# SCH__V2_0.net
KiCad netlist of a schematic drawn in EasyEDA
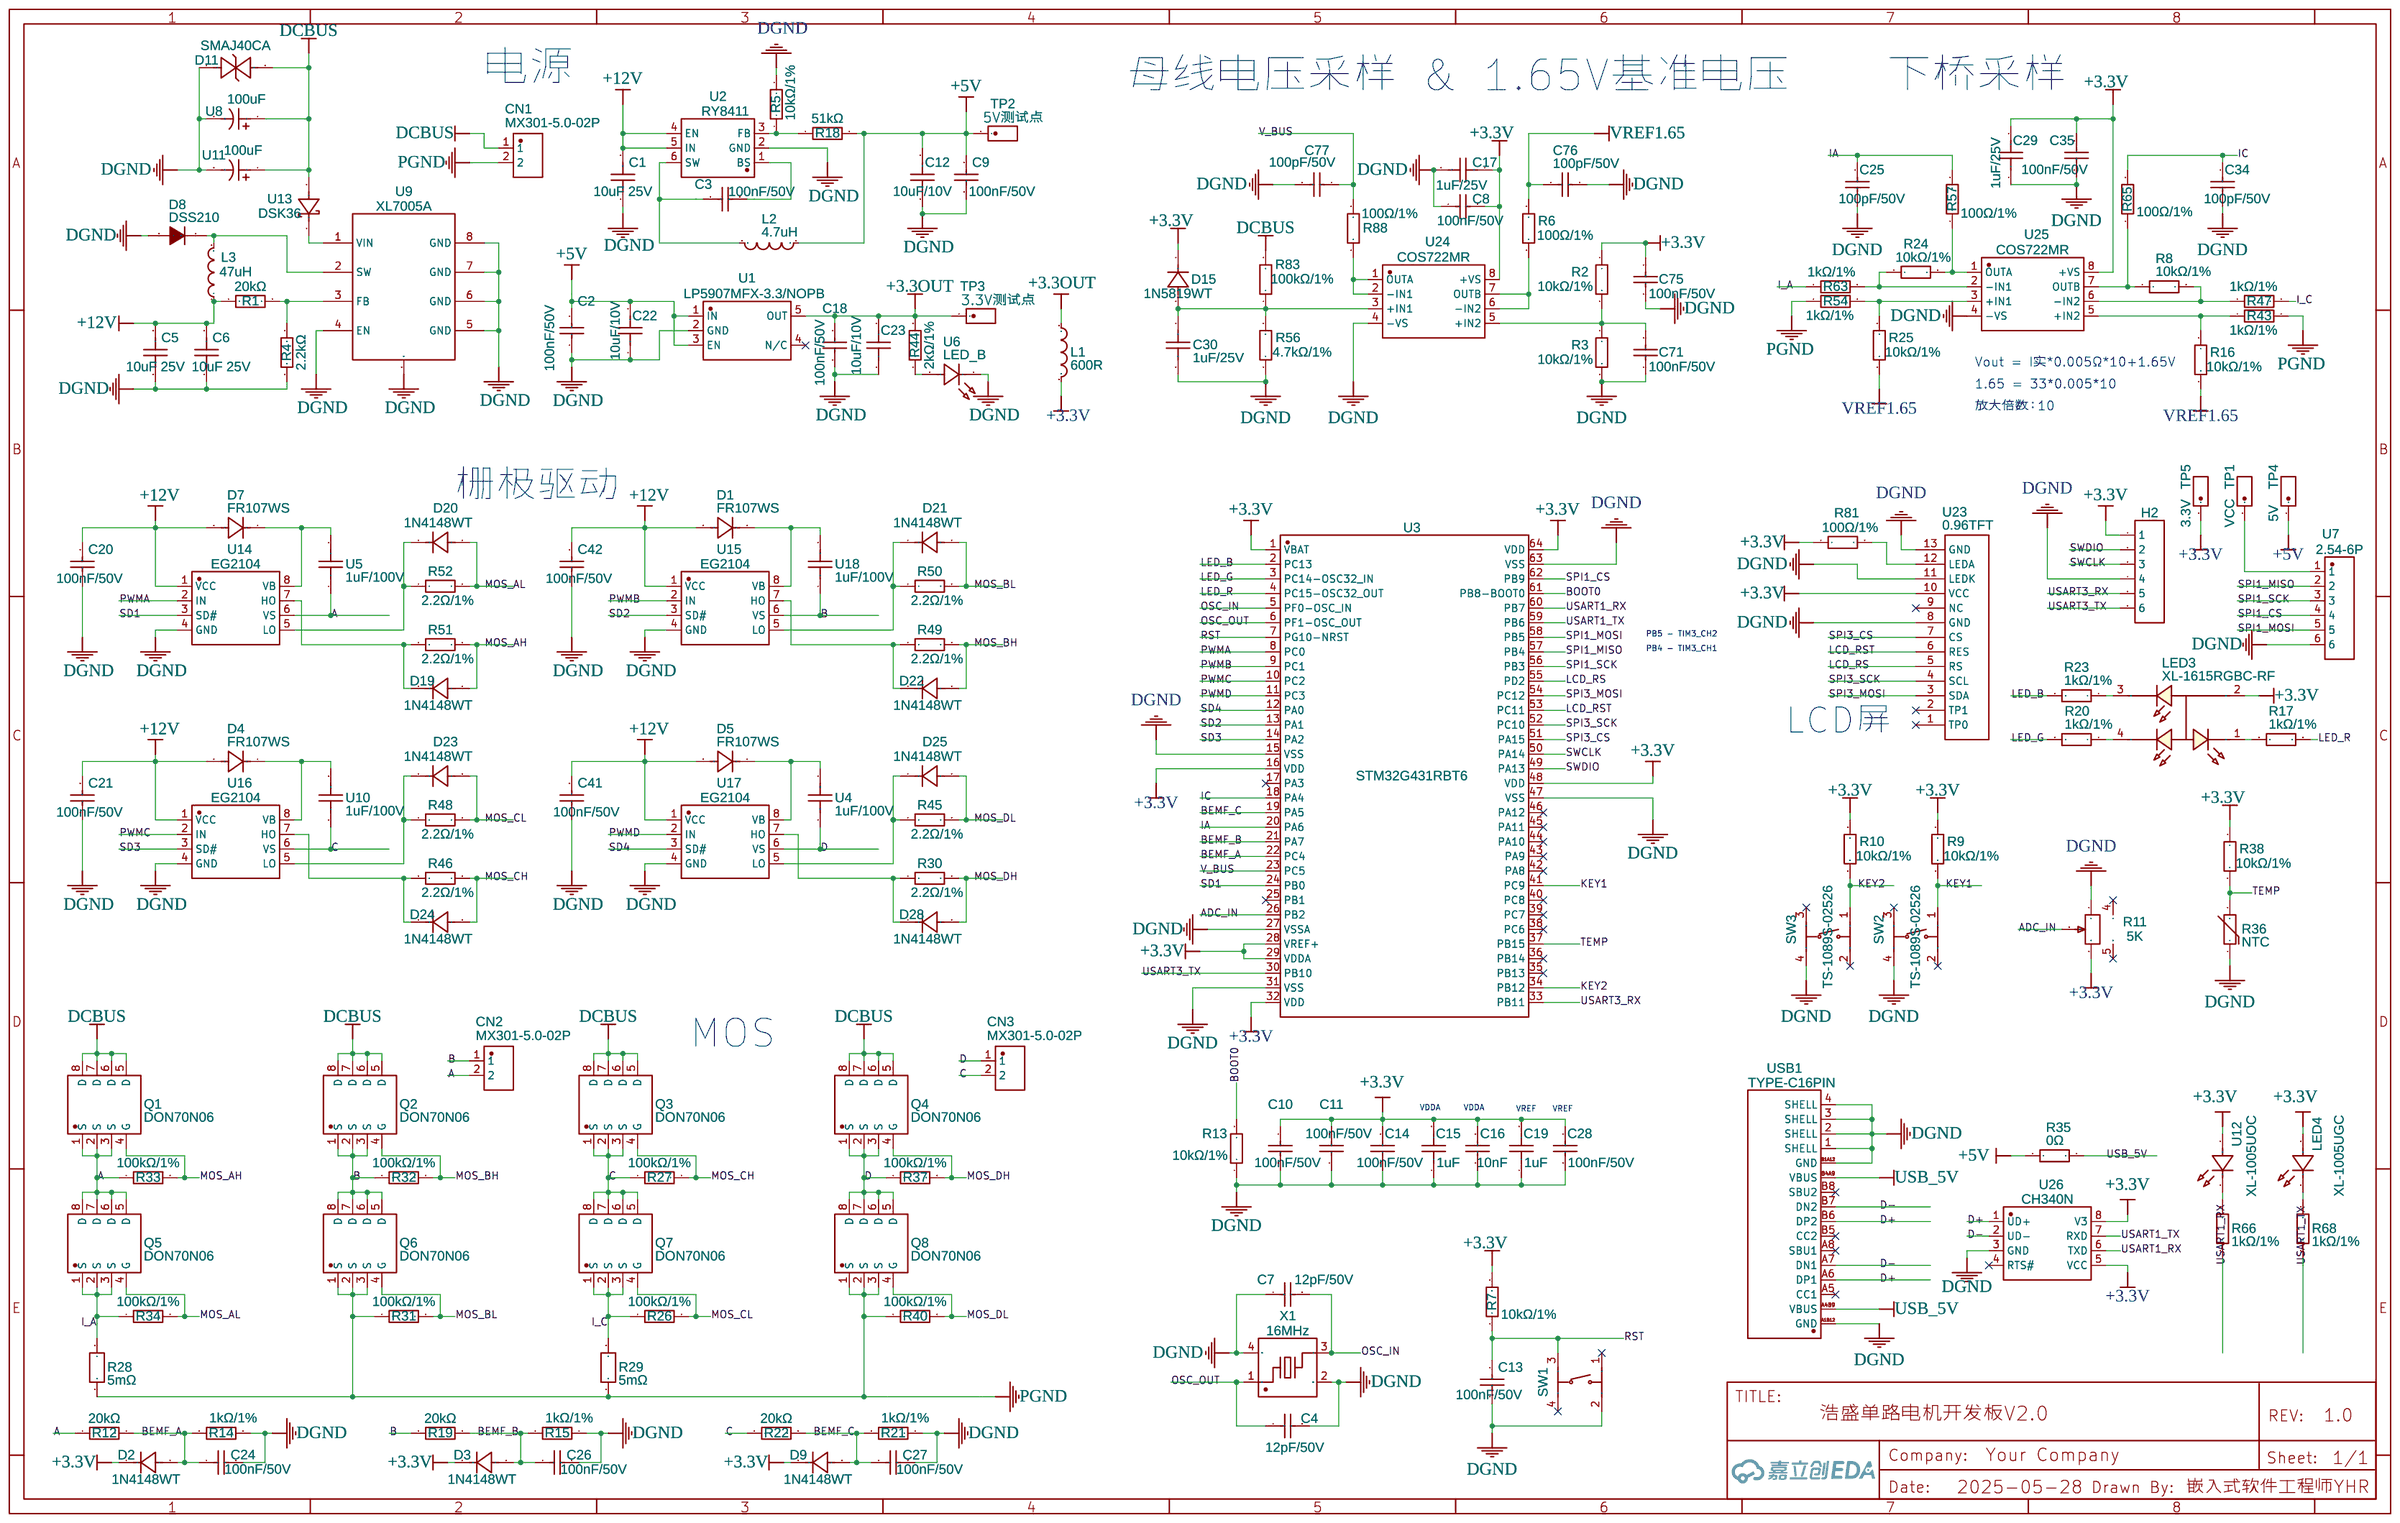
[diagram p0: schematic sheet]

(export (version "E")
  (design (tool "Eeschema 10.0.6"))
  (components
    (comp (ref "C1")
      (value "10uF 25V")
      (fields
        (field (name "Manufacturer Part") "HGC0603R5106M250NTHJ")
        (field (name "Manufacturer") "Chinocera(华瓷)")
      )
      (libsource (lib "") (part "HGC0603R5106M250NTHJ"))
    )
    (comp (ref "C2")
      (value "100nF/50V")
      (fields
        (field (name "Manufacturer Part") "CC0402KRX7R9BB104")
        (field (name "Manufacturer") "YAGEO(国巨)")
      )
      (libsource (lib "") (part "CC0402KRX7R9BB104"))
    )
    (comp (ref "C3")
      (value "100nF/50V")
      (fields
        (field (name "Manufacturer Part") "CC0402KRX7R9BB104")
        (field (name "Manufacturer") "YAGEO(国巨)")
      )
      (libsource (lib "") (part "CC0402KRX7R9BB104_3"))
    )
    (comp (ref "C4")
      (value "12pF/50V")
      (fields
        (field (name "Manufacturer Part") "CC0402JRNPO9BN120")
        (field (name "Manufacturer") "YAGEO(国巨)")
      )
      (libsource (lib "") (part "CC0402JRNPO9BN120"))
    )
    (comp (ref "C5")
      (value "10uF 25V")
      (fields
        (field (name "Manufacturer Part") "HGC0603R5106M250NTHJ")
        (field (name "Manufacturer") "Chinocera(华瓷)")
      )
      (libsource (lib "") (part "HGC0603R5106M250NTHJ"))
    )
    (comp (ref "C6")
      (value "10uF 25V")
      (fields
        (field (name "Manufacturer Part") "HGC0603R5106M250NTHJ")
        (field (name "Manufacturer") "Chinocera(华瓷)")
      )
      (libsource (lib "") (part "HGC0603R5106M250NTHJ"))
    )
    (comp (ref "C7")
      (value "12pF/50V")
      (fields
        (field (name "Manufacturer Part") "CC0402JRNPO9BN120")
        (field (name "Manufacturer") "YAGEO(国巨)")
      )
      (libsource (lib "") (part "CC0402JRNPO9BN120"))
    )
    (comp (ref "C8")
      (value "100nF/50V")
      (fields
        (field (name "Manufacturer Part") "CC0402KRX7R9BB104")
        (field (name "Manufacturer") "YAGEO(国巨)")
      )
      (libsource (lib "") (part "CC0402KRX7R9BB104_1"))
    )
    (comp (ref "C9")
      (value "100nF/50V")
      (fields
        (field (name "Manufacturer Part") "CC0402KRX7R9BB104")
        (field (name "Manufacturer") "YAGEO(国巨)")
      )
      (libsource (lib "") (part "CC0402KRX7R9BB104"))
    )
    (comp (ref "C10")
      (value "100nF/50V")
      (fields
        (field (name "Manufacturer Part") "CC0402KRX7R9BB104")
        (field (name "Manufacturer") "YAGEO(国巨)")
      )
      (libsource (lib "") (part "CC0402KRX7R9BB104"))
    )
    (comp (ref "C11")
      (value "100nF/50V")
      (fields
        (field (name "Manufacturer Part") "CC0402KRX7R9BB104")
        (field (name "Manufacturer") "YAGEO(国巨)")
      )
      (libsource (lib "") (part "CC0402KRX7R9BB104"))
    )
    (comp (ref "C12")
      (value "10uF/10V")
      (fields
        (field (name "Manufacturer Part") "CL05A106MP5NUNC")
        (field (name "Manufacturer") "SAMSUNG(三星)")
      )
      (libsource (lib "") (part "CL05A106MP5NUNC_C315248"))
    )
    (comp (ref "C13")
      (value "100nF/50V")
      (fields
        (field (name "Manufacturer Part") "CC0402KRX7R9BB104")
        (field (name "Manufacturer") "YAGEO(国巨)")
      )
      (libsource (lib "") (part "CC0402KRX7R9BB104_2"))
    )
    (comp (ref "C14")
      (value "100nF/50V")
      (fields
        (field (name "Manufacturer Part") "CC0402KRX7R9BB104")
        (field (name "Manufacturer") "YAGEO(国巨)")
      )
      (libsource (lib "") (part "CC0402KRX7R9BB104"))
    )
    (comp (ref "C15")
      (value "1uF")
      (fields
        (field (name "Manufacturer Part") "CC0402KRX5R8BB105")
        (field (name "Manufacturer") "YAGEO(国巨)")
      )
      (libsource (lib "") (part "CC0402KRX5R8BB105"))
    )
    (comp (ref "C16")
      (value "10nF")
      (fields
        (field (name "Manufacturer Part") "CC0402KRX7R9BB103")
        (field (name "Manufacturer") "YAGEO(国巨)")
      )
      (libsource (lib "") (part "CC0402KRX7R9BB103"))
    )
    (comp (ref "C17")
      (value "1uF/25V")
      (fields
        (field (name "Manufacturer Part") "CL05A105KA5NQNC")
        (field (name "Manufacturer") "SAMSUNG(三星)")
      )
      (libsource (lib "") (part "CL05A105KA5NQNC_2"))
    )
    (comp (ref "C18")
      (value "100nF/50V")
      (fields
        (field (name "Manufacturer Part") "CC0402KRX7R9BB104")
        (field (name "Manufacturer") "YAGEO(国巨)")
      )
      (libsource (lib "") (part "CC0402KRX7R9BB104"))
    )
    (comp (ref "C19")
      (value "1uF")
      (fields
        (field (name "Manufacturer Part") "CC0402KRX5R8BB105")
        (field (name "Manufacturer") "YAGEO(国巨)")
      )
      (libsource (lib "") (part "CC0402KRX5R8BB105"))
    )
    (comp (ref "C20")
      (value "100nF/50V")
      (fields
        (field (name "Manufacturer Part") "CC0402KRX7R9BB104")
        (field (name "Manufacturer") "YAGEO(国巨)")
      )
      (libsource (lib "") (part "CC0402KRX7R9BB104"))
    )
    (comp (ref "C21")
      (value "100nF/50V")
      (fields
        (field (name "Manufacturer Part") "CC0402KRX7R9BB104")
        (field (name "Manufacturer") "YAGEO(国巨)")
      )
      (libsource (lib "") (part "CC0402KRX7R9BB104"))
    )
    (comp (ref "C22")
      (value "10uF/10V")
      (fields
        (field (name "Manufacturer Part") "CL05A106MP5NUNC")
        (field (name "Manufacturer") "SAMSUNG(三星)")
      )
      (libsource (lib "") (part "CL05A106MP5NUNC_C315248"))
    )
    (comp (ref "C23")
      (value "10uF/10V")
      (fields
        (field (name "Manufacturer Part") "CL05A106MP5NUNC")
        (field (name "Manufacturer") "SAMSUNG(三星)")
      )
      (libsource (lib "") (part "CL05A106MP5NUNC_C315248_1"))
    )
    (comp (ref "C24")
      (value "100nF/50V")
      (fields
        (field (name "Manufacturer Part") "CC0402KRX7R9BB104")
        (field (name "Manufacturer") "YAGEO(国巨)")
      )
      (libsource (lib "") (part "CC0402KRX7R9BB104_1"))
    )
    (comp (ref "C25")
      (value "100pF/50V")
      (fields
        (field (name "Manufacturer Part") "CC0402JRNPO9BN101")
        (field (name "Manufacturer") "YAGEO(国巨)")
      )
      (libsource (lib "") (part "CC0402JRNPO9BN101"))
    )
    (comp (ref "C26")
      (value "100nF/50V")
      (fields
        (field (name "Manufacturer Part") "CC0402KRX7R9BB104")
        (field (name "Manufacturer") "YAGEO(国巨)")
      )
      (libsource (lib "") (part "CC0402KRX7R9BB104_1"))
    )
    (comp (ref "C27")
      (value "100nF/50V")
      (fields
        (field (name "Manufacturer Part") "CC0402KRX7R9BB104")
        (field (name "Manufacturer") "YAGEO(国巨)")
      )
      (libsource (lib "") (part "CC0402KRX7R9BB104_1"))
    )
    (comp (ref "C28")
      (value "100nF/50V")
      (fields
        (field (name "Manufacturer Part") "CC0402KRX7R9BB104")
        (field (name "Manufacturer") "YAGEO(国巨)")
      )
      (libsource (lib "") (part "CC0402KRX7R9BB104"))
    )
    (comp (ref "C29")
      (value "1uF/25V")
      (fields
        (field (name "Manufacturer Part") "CL05A105KA5NQNC")
        (field (name "Manufacturer") "SAMSUNG(三星)")
      )
      (libsource (lib "") (part "CL05A105KA5NQNC"))
    )
    (comp (ref "C30")
      (value "1uF/25V")
      (fields
        (field (name "Manufacturer Part") "CL05A105KA5NQNC")
        (field (name "Manufacturer") "SAMSUNG(三星)")
      )
      (libsource (lib "") (part "CL05A105KA5NQNC_1"))
    )
    (comp (ref "C34")
      (value "100pF/50V")
      (fields
        (field (name "Manufacturer Part") "CC0402JRNPO9BN101")
        (field (name "Manufacturer") "YAGEO(国巨)")
      )
      (libsource (lib "") (part "CC0402JRNPO9BN101"))
    )
    (comp (ref "C35")
      (value "100nF/50V")
      (fields
        (field (name "Manufacturer Part") "CC0402KRX7R9BB104")
        (field (name "Manufacturer") "YAGEO(国巨)")
      )
      (libsource (lib "") (part "CC0402KRX7R9BB104_2"))
    )
    (comp (ref "C41")
      (value "100nF/50V")
      (fields
        (field (name "Manufacturer Part") "CC0402KRX7R9BB104")
        (field (name "Manufacturer") "YAGEO(国巨)")
      )
      (libsource (lib "") (part "CC0402KRX7R9BB104"))
    )
    (comp (ref "C42")
      (value "100nF/50V")
      (fields
        (field (name "Manufacturer Part") "CC0402KRX7R9BB104")
        (field (name "Manufacturer") "YAGEO(国巨)")
      )
      (libsource (lib "") (part "CC0402KRX7R9BB104"))
    )
    (comp (ref "C71")
      (value "100nF/50V")
      (fields
        (field (name "Manufacturer Part") "CC0402KRX7R9BB104")
        (field (name "Manufacturer") "YAGEO(国巨)")
      )
      (libsource (lib "") (part "CC0402KRX7R9BB104"))
    )
    (comp (ref "C75")
      (value "100nF/50V")
      (fields
        (field (name "Manufacturer Part") "CC0402KRX7R9BB104")
        (field (name "Manufacturer") "YAGEO(国巨)")
      )
      (libsource (lib "") (part "CC0402KRX7R9BB104"))
    )
    (comp (ref "C76")
      (value "100pF/50V")
      (fields
        (field (name "Manufacturer Part") "CC0402JRNPO9BN101")
        (field (name "Manufacturer") "YAGEO(国巨)")
      )
      (libsource (lib "") (part "CC0402JRNPO9BN101_1"))
    )
    (comp (ref "C77")
      (value "100pF/50V")
      (fields
        (field (name "Manufacturer Part") "CC0402JRNPO9BN101")
        (field (name "Manufacturer") "YAGEO(国巨)")
      )
      (libsource (lib "") (part "CC0402JRNPO9BN101_1"))
    )
    (comp (ref "CN1")
      (value "MX301-5.0-02P")
      (fields
        (field (name "Manufacturer Part") "MX301-5.0-02P-BU01-Cu-Y-A")
        (field (name "Manufacturer") "MAX(迈旭)")
      )
      (libsource (lib "") (part "MX301-5.0-02P-BU01-CU-Y-A"))
    )
    (comp (ref "CN2")
      (value "MX301-5.0-02P")
      (fields
        (field (name "Manufacturer Part") "MX301-5.0-02P-BU01-Cu-Y-A")
        (field (name "Manufacturer") "MAX(迈旭)")
      )
      (libsource (lib "") (part "MX301-5.0-02P-BU01-CU-Y-A"))
    )
    (comp (ref "CN3")
      (value "MX301-5.0-02P")
      (fields
        (field (name "Manufacturer Part") "MX301-5.0-02P-BU01-Cu-Y-A")
        (field (name "Manufacturer") "MAX(迈旭)")
      )
      (libsource (lib "") (part "MX301-5.0-02P-BU01-CU-Y-A"))
    )
    (comp (ref "D1")
      (value "FR107WS")
      (fields (field (name "Manufacturer") "YFW(佑风微)"))
      (libsource (lib "") (part "FR107WS_C3013756"))
    )
    (comp (ref "D2")
      (value "1N4148WT")
      (fields (field (name "Manufacturer") "TECH PUBLIC(台舟)"))
      (libsource (lib "") (part "1N4148WT_C708767"))
    )
    (comp (ref "D3")
      (value "1N4148WT")
      (fields (field (name "Manufacturer") "TECH PUBLIC(台舟)"))
      (libsource (lib "") (part "1N4148WT_C708767"))
    )
    (comp (ref "D4")
      (value "FR107WS")
      (fields (field (name "Manufacturer") "YFW(佑风微)"))
      (libsource (lib "") (part "FR107WS_C3013756"))
    )
    (comp (ref "D5")
      (value "FR107WS")
      (fields (field (name "Manufacturer") "YFW(佑风微)"))
      (libsource (lib "") (part "FR107WS_C3013756"))
    )
    (comp (ref "D7")
      (value "FR107WS")
      (fields (field (name "Manufacturer") "YFW(佑风微)"))
      (libsource (lib "") (part "FR107WS_C3013756"))
    )
    (comp (ref "D8")
      (value "DSS210")
      (fields (field (name "Manufacturer") "BORN(伯恩半导体)"))
      (libsource (lib "") (part "DSS210"))
    )
    (comp (ref "D9")
      (value "1N4148WT")
      (fields (field (name "Manufacturer") "TECH PUBLIC(台舟)"))
      (libsource (lib "") (part "1N4148WT_C708767"))
    )
    (comp (ref "D11")
      (value "SMAJ40CA")
      (fields (field (name "Manufacturer") "宏嘉诚"))
      (libsource (lib "") (part "SMAJ40CA_C19077552"))
    )
    (comp (ref "D15")
      (value "1N5819WT")
      (fields (field (name "Manufacturer") "HXY MOSFET(华轩阳电子)"))
      (libsource (lib "") (part "1N5819WT_C5451630"))
    )
    (comp (ref "D19")
      (value "1N4148WT")
      (fields (field (name "Manufacturer") "TECH PUBLIC(台舟)"))
      (libsource (lib "") (part "1N4148WT_C708767"))
    )
    (comp (ref "D20")
      (value "1N4148WT")
      (fields (field (name "Manufacturer") "TECH PUBLIC(台舟)"))
      (libsource (lib "") (part "1N4148WT_C708767"))
    )
    (comp (ref "D21")
      (value "1N4148WT")
      (fields (field (name "Manufacturer") "TECH PUBLIC(台舟)"))
      (libsource (lib "") (part "1N4148WT_C708767"))
    )
    (comp (ref "D22")
      (value "1N4148WT")
      (fields (field (name "Manufacturer") "TECH PUBLIC(台舟)"))
      (libsource (lib "") (part "1N4148WT_C708767"))
    )
    (comp (ref "D23")
      (value "1N4148WT")
      (fields (field (name "Manufacturer") "TECH PUBLIC(台舟)"))
      (libsource (lib "") (part "1N4148WT_C708767"))
    )
    (comp (ref "D24")
      (value "1N4148WT")
      (fields (field (name "Manufacturer") "TECH PUBLIC(台舟)"))
      (libsource (lib "") (part "1N4148WT_C708767"))
    )
    (comp (ref "D25")
      (value "1N4148WT")
      (fields (field (name "Manufacturer") "TECH PUBLIC(台舟)"))
      (libsource (lib "") (part "1N4148WT_C708767"))
    )
    (comp (ref "D28")
      (value "1N4148WT")
      (fields (field (name "Manufacturer") "TECH PUBLIC(台舟)"))
      (libsource (lib "") (part "1N4148WT_C708767"))
    )
    (comp (ref "H2")
      (value "Header-Male-2.54_1x6")
      (fields (field (name "Manufacturer Part") "2.54-1x6P直针") (field (name "Manufacturer") "BOOMELE(博穆精密)"))
      (libsource (lib "") (part "Header-Male-2.54_1x6"))
    )
    (comp (ref "L1")
      (value "600R")
      (fields (field (name "Manufacturer Part") "BLM15AG601SN1D") (field (name "Manufacturer") "muRata(村田)"))
      (libsource (lib "") (part "BLM15AG601SN1D"))
    )
    (comp (ref "L2")
      (value "4.7uH")
      (fields
        (field (name "Manufacturer Part") "FHD4020S-4R7MT")
        (field (name "Manufacturer") "cjiang(长江微电)")
      )
      (libsource (lib "") (part "FHD4020S-4R7MT"))
    )
    (comp (ref "L3")
      (value "47uH")
      (fields
        (field (name "Manufacturer Part") "FHD4020S-470MT")
        (field (name "Manufacturer") "cjiang(长江微电)")
      )
      (libsource (lib "") (part "FHD4020S-470MT"))
    )
    (comp (ref "LED3")
      (value "XL-1615RGBC-RF")
      (fields (field (name "Manufacturer") "XINGLIGHT(成兴光)"))
      (libsource (lib "") (part "XL-1615RGBC-RF"))
    )
    (comp (ref "LED4")
      (value "XL-1005UGC")
      (fields (field (name "Manufacturer") "XINGLIGHT(成兴光)"))
      (libsource (lib "") (part "XL-1005UGC"))
    )
    (comp (ref "Q1")
      (value "DON70N06")
      (fields (field (name "Manufacturer") "DOINGTER(杜因特)"))
      (libsource (lib "") (part "DON70N06"))
    )
    (comp (ref "Q2")
      (value "DON70N06")
      (fields (field (name "Manufacturer") "DOINGTER(杜因特)"))
      (libsource (lib "") (part "DON70N06"))
    )
    (comp (ref "Q3")
      (value "DON70N06")
      (fields (field (name "Manufacturer") "DOINGTER(杜因特)"))
      (libsource (lib "") (part "DON70N06"))
    )
    (comp (ref "Q4")
      (value "DON70N06")
      (fields (field (name "Manufacturer") "DOINGTER(杜因特)"))
      (libsource (lib "") (part "DON70N06"))
    )
    (comp (ref "Q5")
      (value "DON70N06")
      (fields (field (name "Manufacturer") "DOINGTER(杜因特)"))
      (libsource (lib "") (part "DON70N06"))
    )
    (comp (ref "Q6")
      (value "DON70N06")
      (fields (field (name "Manufacturer") "DOINGTER(杜因特)"))
      (libsource (lib "") (part "DON70N06"))
    )
    (comp (ref "Q7")
      (value "DON70N06")
      (fields (field (name "Manufacturer") "DOINGTER(杜因特)"))
      (libsource (lib "") (part "DON70N06"))
    )
    (comp (ref "Q8")
      (value "DON70N06")
      (fields (field (name "Manufacturer") "DOINGTER(杜因特)"))
      (libsource (lib "") (part "DON70N06"))
    )
    (comp (ref "R1")
      (value "20kΩ")
      (fields (field (name "Manufacturer Part") "RC0402FR-0720KL") (field (name "Manufacturer") "YAGEO(国巨)"))
      (libsource (lib "") (part "RC0402FR-0720KL"))
    )
    (comp (ref "R2")
      (value "10kΩ/1%")
      (fields (field (name "Manufacturer Part") "RC0402FR-0710KL") (field (name "Manufacturer") "YAGEO(国巨)"))
      (libsource (lib "") (part "RC0402FR-0710KL"))
    )
    (comp (ref "R3")
      (value "10kΩ/1%")
      (fields (field (name "Manufacturer Part") "RC0402FR-0710KL") (field (name "Manufacturer") "YAGEO(国巨)"))
      (libsource (lib "") (part "RC0402FR-0710KL"))
    )
    (comp (ref "R4")
      (value "2.2kΩ")
      (fields (field (name "Manufacturer Part") "RC0402FR-072K2L") (field (name "Manufacturer") "YAGEO(国巨)"))
      (libsource (lib "") (part "RC0402FR-072K2L"))
    )
    (comp (ref "R5")
      (value "10kΩ/1%")
      (fields (field (name "Manufacturer Part") "RC0402FR-0710KL") (field (name "Manufacturer") "YAGEO(国巨)"))
      (libsource (lib "") (part "RC0402FR-0710KL_1"))
    )
    (comp (ref "R6")
      (value "100Ω/1%")
      (fields (field (name "Manufacturer Part") "RC0402FR-07100RL") (field (name "Manufacturer") "YAGEO(国巨)"))
      (libsource (lib "") (part "RC0402FR-07100RL"))
    )
    (comp (ref "R7")
      (value "10kΩ/1%")
      (fields (field (name "Manufacturer Part") "RC0402FR-0710KL") (field (name "Manufacturer") "YAGEO(国巨)"))
      (libsource (lib "") (part "RC0402FR-0710KL_1"))
    )
    (comp (ref "R8")
      (value "10kΩ/1%")
      (fields (field (name "Manufacturer Part") "RC0402FR-0710KL") (field (name "Manufacturer") "YAGEO(国巨)"))
      (libsource (lib "") (part "RC0402FR-0710KL_2"))
    )
    (comp (ref "R9")
      (value "10kΩ/1%")
      (fields (field (name "Manufacturer Part") "RC0402FR-0710KL") (field (name "Manufacturer") "YAGEO(国巨)"))
      (libsource (lib "") (part "RC0402FR-0710KL"))
    )
    (comp (ref "R10")
      (value "10kΩ/1%")
      (fields (field (name "Manufacturer Part") "RC0402FR-0710KL") (field (name "Manufacturer") "YAGEO(国巨)"))
      (libsource (lib "") (part "RC0402FR-0710KL"))
    )
    (comp (ref "R11")
      (value "5K")
      (fields (field (name "Manufacturer Part") "R1001-B502-3P 18mm"))
      (libsource (lib "") (part "R1001-B502-3P 18mm"))
    )
    (comp (ref "R12")
      (value "20kΩ")
      (fields (field (name "Manufacturer Part") "RC0402FR-0720KL") (field (name "Manufacturer") "YAGEO(国巨)"))
      (libsource (lib "") (part "RC0402FR-0720KL"))
    )
    (comp (ref "R13")
      (value "10kΩ/1%")
      (fields (field (name "Manufacturer Part") "RC0402FR-0710KL") (field (name "Manufacturer") "YAGEO(国巨)"))
      (libsource (lib "") (part "RC0402FR-0710KL_1"))
    )
    (comp (ref "R14")
      (value "1kΩ/1%")
      (fields (field (name "Manufacturer Part") "RC0402FR-071KL") (field (name "Manufacturer") "YAGEO(国巨)"))
      (libsource (lib "") (part "RC0402FR-071KL_1"))
    )
    (comp (ref "R15")
      (value "1kΩ/1%")
      (fields (field (name "Manufacturer Part") "RC0402FR-071KL") (field (name "Manufacturer") "YAGEO(国巨)"))
      (libsource (lib "") (part "RC0402FR-071KL_1"))
    )
    (comp (ref "R16")
      (value "10kΩ/1%")
      (fields (field (name "Manufacturer Part") "RC0402FR-0710KL") (field (name "Manufacturer") "YAGEO(国巨)"))
      (libsource (lib "") (part "RC0402FR-0710KL"))
    )
    (comp (ref "R17")
      (value "1kΩ/1%")
      (fields (field (name "Manufacturer Part") "RC0402FR-071KL") (field (name "Manufacturer") "YAGEO(国巨)"))
      (libsource (lib "") (part "RC0402FR-071KL_1"))
    )
    (comp (ref "R18")
      (value "51kΩ")
      (fields (field (name "Manufacturer Part") "RC0402FR-0751KL") (field (name "Manufacturer") "YAGEO(国巨)"))
      (libsource (lib "") (part "RC0402FR-0751KL"))
    )
    (comp (ref "R19")
      (value "20kΩ")
      (fields (field (name "Manufacturer Part") "RC0402FR-0720KL") (field (name "Manufacturer") "YAGEO(国巨)"))
      (libsource (lib "") (part "RC0402FR-0720KL"))
    )
    (comp (ref "R20")
      (value "1kΩ/1%")
      (fields (field (name "Manufacturer Part") "RC0402FR-071KL") (field (name "Manufacturer") "YAGEO(国巨)"))
      (libsource (lib "") (part "RC0402FR-071KL_1"))
    )
    (comp (ref "R21")
      (value "1kΩ/1%")
      (fields (field (name "Manufacturer Part") "RC0402FR-071KL") (field (name "Manufacturer") "YAGEO(国巨)"))
      (libsource (lib "") (part "RC0402FR-071KL_1"))
    )
    (comp (ref "R22")
      (value "20kΩ")
      (fields (field (name "Manufacturer Part") "RC0402FR-0720KL") (field (name "Manufacturer") "YAGEO(国巨)"))
      (libsource (lib "") (part "RC0402FR-0720KL"))
    )
    (comp (ref "R23")
      (value "1kΩ/1%")
      (fields (field (name "Manufacturer Part") "RC0402FR-071KL") (field (name "Manufacturer") "YAGEO(国巨)"))
      (libsource (lib "") (part "RC0402FR-071KL_1"))
    )
    (comp (ref "R24")
      (value "10kΩ/1%")
      (fields (field (name "Manufacturer Part") "RC0402FR-0710KL") (field (name "Manufacturer") "YAGEO(国巨)"))
      (libsource (lib "") (part "RC0402FR-0710KL_2"))
    )
    (comp (ref "R25")
      (value "10kΩ/1%")
      (fields (field (name "Manufacturer Part") "RC0402FR-0710KL") (field (name "Manufacturer") "YAGEO(国巨)"))
      (libsource (lib "") (part "RC0402FR-0710KL"))
    )
    (comp (ref "R26")
      (value "100kΩ/1%")
      (fields (field (name "Manufacturer Part") "RC0402FR-07100KL") (field (name "Manufacturer") "YAGEO(国巨)"))
      (libsource (lib "") (part "RC0402FR-07100KL"))
    )
    (comp (ref "R27")
      (value "100kΩ/1%")
      (fields (field (name "Manufacturer Part") "RC0402FR-07100KL") (field (name "Manufacturer") "YAGEO(国巨)"))
      (libsource (lib "") (part "RC0402FR-07100KL"))
    )
    (comp (ref "R28")
      (value "5mΩ")
      (fields
        (field (name "Manufacturer Part") "HoJLR2512-3W-5mR-1%")
        (field (name "Manufacturer") "Milliohm(毫欧)")
      )
      (libsource (lib "") (part "HOJLR2512-3W-5MR-1%"))
    )
    (comp (ref "R29")
      (value "5mΩ")
      (fields
        (field (name "Manufacturer Part") "HoJLR2512-3W-5mR-1%")
        (field (name "Manufacturer") "Milliohm(毫欧)")
      )
      (libsource (lib "") (part "HOJLR2512-3W-5MR-1%"))
    )
    (comp (ref "R30")
      (value "2.2Ω/1%")
      (fields (field (name "Manufacturer Part") "RC0402FR-072R2L") (field (name "Manufacturer") "YAGEO(国巨)"))
      (libsource (lib "") (part "RC0402FR-072R2L"))
    )
    (comp (ref "R31")
      (value "100kΩ/1%")
      (fields (field (name "Manufacturer Part") "RC0402FR-07100KL") (field (name "Manufacturer") "YAGEO(国巨)"))
      (libsource (lib "") (part "RC0402FR-07100KL"))
    )
    (comp (ref "R32")
      (value "100kΩ/1%")
      (fields (field (name "Manufacturer Part") "RC0402FR-07100KL") (field (name "Manufacturer") "YAGEO(国巨)"))
      (libsource (lib "") (part "RC0402FR-07100KL"))
    )
    (comp (ref "R33")
      (value "100kΩ/1%")
      (fields (field (name "Manufacturer Part") "RC0402FR-07100KL") (field (name "Manufacturer") "YAGEO(国巨)"))
      (libsource (lib "") (part "RC0402FR-07100KL"))
    )
    (comp (ref "R34")
      (value "100kΩ/1%")
      (fields (field (name "Manufacturer Part") "RC0402FR-07100KL") (field (name "Manufacturer") "YAGEO(国巨)"))
      (libsource (lib "") (part "RC0402FR-07100KL"))
    )
    (comp (ref "R35")
      (value "0Ω")
      (fields
        (field (name "Manufacturer Part") "0402WGF0000TCE")
        (field (name "Manufacturer") "UNI-ROYAL(厚声)")
      )
      (libsource (lib "") (part "0402WGF0000TCE"))
    )
    (comp (ref "R36")
      (value "NTC")
      (fields (field (name "Manufacturer Part") "NCP15XH103F03RC") (field (name "Manufacturer") "muRata(村田)"))
      (libsource (lib "") (part "NCP15XH103F03RC"))
    )
    (comp (ref "R37")
      (value "100kΩ/1%")
      (fields (field (name "Manufacturer Part") "RC0402FR-07100KL") (field (name "Manufacturer") "YAGEO(国巨)"))
      (libsource (lib "") (part "RC0402FR-07100KL"))
    )
    (comp (ref "R38")
      (value "10kΩ/1%")
      (fields (field (name "Manufacturer Part") "RC0402FR-0710KL") (field (name "Manufacturer") "YAGEO(国巨)"))
      (libsource (lib "") (part "RC0402FR-0710KL"))
    )
    (comp (ref "R40")
      (value "100kΩ/1%")
      (fields (field (name "Manufacturer Part") "RC0402FR-07100KL") (field (name "Manufacturer") "YAGEO(国巨)"))
      (libsource (lib "") (part "RC0402FR-07100KL"))
    )
    (comp (ref "R43")
      (value "1kΩ/1%")
      (fields (field (name "Manufacturer Part") "RC0402FR-071KL") (field (name "Manufacturer") "YAGEO(国巨)"))
      (libsource (lib "") (part "RT0402BRD071K5L"))
    )
    (comp (ref "R44")
      (value "2kΩ/1%")
      (fields (field (name "Manufacturer Part") "RC0402FR-072KL") (field (name "Manufacturer") "YAGEO(国巨)"))
      (libsource (lib "") (part "RC0402FR-072KL"))
    )
    (comp (ref "R45")
      (value "2.2Ω/1%")
      (fields (field (name "Manufacturer Part") "RC0402FR-072R2L") (field (name "Manufacturer") "YAGEO(国巨)"))
      (libsource (lib "") (part "RC0402FR-072R2L"))
    )
    (comp (ref "R46")
      (value "2.2Ω/1%")
      (fields (field (name "Manufacturer Part") "RC0402FR-072R2L") (field (name "Manufacturer") "YAGEO(国巨)"))
      (libsource (lib "") (part "RC0402FR-072R2L"))
    )
    (comp (ref "R47")
      (value "1kΩ/1%")
      (fields (field (name "Manufacturer Part") "RC0402FR-071KL") (field (name "Manufacturer") "YAGEO(国巨)"))
      (libsource (lib "") (part "RT0402BRD071K5L"))
    )
    (comp (ref "R48")
      (value "2.2Ω/1%")
      (fields (field (name "Manufacturer Part") "RC0402FR-072R2L") (field (name "Manufacturer") "YAGEO(国巨)"))
      (libsource (lib "") (part "RC0402FR-072R2L"))
    )
    (comp (ref "R49")
      (value "2.2Ω/1%")
      (fields (field (name "Manufacturer Part") "RC0402FR-072R2L") (field (name "Manufacturer") "YAGEO(国巨)"))
      (libsource (lib "") (part "RC0402FR-072R2L"))
    )
    (comp (ref "R50")
      (value "2.2Ω/1%")
      (fields (field (name "Manufacturer Part") "RC0402FR-072R2L") (field (name "Manufacturer") "YAGEO(国巨)"))
      (libsource (lib "") (part "RC0402FR-072R2L"))
    )
    (comp (ref "R51")
      (value "2.2Ω/1%")
      (fields (field (name "Manufacturer Part") "RC0402FR-072R2L") (field (name "Manufacturer") "YAGEO(国巨)"))
      (libsource (lib "") (part "RC0402FR-072R2L"))
    )
    (comp (ref "R52")
      (value "2.2Ω/1%")
      (fields (field (name "Manufacturer Part") "RC0402FR-072R2L") (field (name "Manufacturer") "YAGEO(国巨)"))
      (libsource (lib "") (part "RC0402FR-072R2L"))
    )
    (comp (ref "R54")
      (value "1kΩ/1%")
      (fields (field (name "Manufacturer Part") "RC0402FR-071KL") (field (name "Manufacturer") "YAGEO(国巨)"))
      (libsource (lib "") (part "RT0402BRD071K5L"))
    )
    (comp (ref "R56")
      (value "4.7kΩ/1%")
      (fields (field (name "Manufacturer Part") "RC0402FR-074K7L") (field (name "Manufacturer") "YAGEO(国巨)"))
      (libsource (lib "") (part "RC0402FR-074K7L"))
    )
    (comp (ref "R57")
      (value "100Ω/1%")
      (fields (field (name "Manufacturer Part") "RC0402FR-07100RL") (field (name "Manufacturer") "YAGEO(国巨)"))
      (libsource (lib "") (part "RC0402FR-07100RL"))
    )
    (comp (ref "R63")
      (value "1kΩ/1%")
      (fields (field (name "Manufacturer Part") "RC0402FR-071KL") (field (name "Manufacturer") "YAGEO(国巨)"))
      (libsource (lib "") (part "RT0402BRD071K5L"))
    )
    (comp (ref "R65")
      (value "100Ω/1%")
      (fields (field (name "Manufacturer Part") "RC0402FR-07100RL") (field (name "Manufacturer") "YAGEO(国巨)"))
      (libsource (lib "") (part "RC0402FR-07100RL"))
    )
    (comp (ref "R66")
      (value "1kΩ/1%")
      (fields (field (name "Manufacturer Part") "RC0402FR-071KL") (field (name "Manufacturer") "YAGEO(国巨)"))
      (libsource (lib "") (part "RC0402FR-071KL"))
    )
    (comp (ref "R68")
      (value "1kΩ/1%")
      (fields (field (name "Manufacturer Part") "RC0402FR-071KL") (field (name "Manufacturer") "YAGEO(国巨)"))
      (libsource (lib "") (part "RC0402FR-071KL"))
    )
    (comp (ref "R81")
      (value "100Ω/1%")
      (fields (field (name "Manufacturer Part") "RC0402FR-07100RL") (field (name "Manufacturer") "YAGEO(国巨)"))
      (libsource (lib "") (part "RC0402FR-07100RL_1"))
    )
    (comp (ref "R83")
      (value "100kΩ/1%")
      (fields (field (name "Manufacturer Part") "RC0402FR-07100KL") (field (name "Manufacturer") "YAGEO(国巨)"))
      (libsource (lib "") (part "RC0402FR-07100KL_1"))
    )
    (comp (ref "R88")
      (value "100Ω/1%")
      (fields (field (name "Manufacturer Part") "RC0402FR-07100RL") (field (name "Manufacturer") "YAGEO(国巨)"))
      (libsource (lib "") (part "RC0402FR-07100RL"))
    )
    (comp (ref "SW1")
      (value "TS-1089S-02526")
      (fields (field (name "Manufacturer") "XUNPU(讯普)"))
      (libsource (lib "") (part "TS-1089S-02526"))
    )
    (comp (ref "SW2")
      (value "TS-1089S-02526")
      (fields (field (name "Manufacturer") "XUNPU(讯普)"))
      (libsource (lib "") (part "TS-1089S-02526"))
    )
    (comp (ref "SW3")
      (value "TS-1089S-02526")
      (fields (field (name "Manufacturer") "XUNPU(讯普)"))
      (libsource (lib "") (part "TS-1089S-02526"))
    )
    (comp (ref "TP1") (value "VCC") (libsource (lib "") (part "测试点")))
    (comp (ref "TP2") (value "5V测试点") (libsource (lib "") (part "测试点_1")))
    (comp (ref "TP3") (value "3.3V测试点") (libsource (lib "") (part "测试点_1")))
    (comp (ref "TP4") (value "5V") (libsource (lib "") (part "测试点")))
    (comp (ref "TP5") (value "3.3V") (libsource (lib "") (part "测试点")))
    (comp (ref "U1")
      (value "LP5907MFX-3.3/NOPB")
      (fields (field (name "Manufacturer") "TI(德州仪器)"))
      (libsource (lib "") (part "LP5907MFX-3.3/NOPB"))
    )
    (comp (ref "U2")
      (value "RY8411")
      (fields (field (name "Manufacturer") "RYCHiP(蕊源)"))
      (libsource (lib "") (part "RY8411_C2935411"))
    )
    (comp (ref "U3")
      (value "STM32G431RBT6")
      (fields (field (name "Manufacturer") "ST(意法半导体)"))
      (libsource (lib "") (part "STM32G431RBT6"))
    )
    (comp (ref "U4")
      (value "1uF/100V")
      (fields
        (field (name "Manufacturer Part") "CC0805KKX7R0BB105")
        (field (name "Manufacturer") "YAGEO(国巨)")
      )
      (libsource (lib "") (part "CC0805KKX7R0BB105"))
    )
    (comp (ref "U5")
      (value "1uF/100V")
      (fields
        (field (name "Manufacturer Part") "CC0805KKX7R0BB105")
        (field (name "Manufacturer") "YAGEO(国巨)")
      )
      (libsource (lib "") (part "CC0805KKX7R0BB105"))
    )
    (comp (ref "U6")
      (value "LED_B")
      (fields (field (name "Manufacturer Part") "XL-1005UBC") (field (name "Manufacturer") "XINGLIGHT(成兴光)"))
      (libsource (lib "") (part "XL-1005UBC_C22355736"))
    )
    (comp (ref "U7")
      (value "2.54-6P")
      (fields
        (field (name "Manufacturer Part") "DB125-2.54-6P-GN-S")
        (field (name "Manufacturer") "DORABO(地博电气)")
      )
      (libsource (lib "") (part "DB125-2.54-6P-GN"))
    )
    (comp (ref "U8")
      (value "100uF")
      (fields (field (name "Manufacturer Part") "189RV0092") (field (name "Manufacturer") "KNSCHA(科尼盛)"))
      (libsource (lib "") (part "189RV0092"))
    )
    (comp (ref "U9")
      (value "XL7005A")
      (fields (field (name "Manufacturer") "XLSEMI(芯龙)"))
      (libsource (lib "") (part "XL7005A"))
    )
    (comp (ref "U10")
      (value "1uF/100V")
      (fields
        (field (name "Manufacturer Part") "CC0805KKX7R0BB105")
        (field (name "Manufacturer") "YAGEO(国巨)")
      )
      (libsource (lib "") (part "CC0805KKX7R0BB105"))
    )
    (comp (ref "U11")
      (value "100uF")
      (fields (field (name "Manufacturer Part") "189RV0092") (field (name "Manufacturer") "KNSCHA(科尼盛)"))
      (libsource (lib "") (part "189RV0092"))
    )
    (comp (ref "U12")
      (value "XL-1005UOC")
      (fields (field (name "Manufacturer") "XINGLIGHT(成兴光)"))
      (libsource (lib "") (part "XL-1005UOC"))
    )
    (comp (ref "U13")
      (value "DSK36")
      (fields (field (name "Manufacturer") "宏嘉诚"))
      (libsource (lib "") (part "DSK36_C22466353"))
    )
    (comp (ref "U14")
      (value "EG2104")
      (fields (field (name "Manufacturer") "EG Micro"))
      (libsource (lib "") (part "EG2104"))
    )
    (comp (ref "U15")
      (value "EG2104")
      (fields (field (name "Manufacturer") "EG Micro"))
      (libsource (lib "") (part "EG2104"))
    )
    (comp (ref "U16")
      (value "EG2104")
      (fields (field (name "Manufacturer") "EG Micro"))
      (libsource (lib "") (part "EG2104"))
    )
    (comp (ref "U17")
      (value "EG2104")
      (fields (field (name "Manufacturer") "EG Micro"))
      (libsource (lib "") (part "EG2104"))
    )
    (comp (ref "U18")
      (value "1uF/100V")
      (fields
        (field (name "Manufacturer Part") "CC0805KKX7R0BB105")
        (field (name "Manufacturer") "YAGEO(国巨)")
      )
      (libsource (lib "") (part "CC0805KKX7R0BB105"))
    )
    (comp (ref "U23") (value "0.96TFT") (libsource (lib "") (part "0.96TFT")))
    (comp (ref "U24")
      (value "COS722MR")
      (fields (field (name "Manufacturer") "COSINE(科山芯创)"))
      (libsource (lib "") (part "COS722MR"))
    )
    (comp (ref "U25")
      (value "COS722MR")
      (fields (field (name "Manufacturer") "COSINE(科山芯创)"))
      (libsource (lib "") (part "COS722MR"))
    )
    (comp (ref "U26")
      (value "CH340N")
      (fields (field (name "Manufacturer") "WCH(Jiangsu Qin Heng)"))
      (libsource (lib "") (part "CH340N"))
    )
    (comp (ref "USB1")
      (value "TYPE-C16PIN")
      (fields (field (name "Manufacturer") "SHOU HAN"))
      (libsource (lib "") (part "TYPE-C16PIN"))
    )
    (comp (ref "X1")
      (value "16MHz")
      (fields
        (field (name "Manufacturer Part") "XL7EL89COI-111YLC-16M")
        (field (name "Manufacturer") "YXC(扬兴晶振)")
      )
      (libsource (lib "") (part "XL7EL89COI-111YLC-16M"))
    )
  )
  (nets
    (net (code "1") (name "+3.3OUT") (class "Default")
      (node (ref "C18") (pin "2") (pinfunction "2_2") (pintype "input"))
      (node (ref "C23") (pin "1") (pinfunction "1_1") (pintype "unspecified"))
      (node (ref "L1") (pin "1") (pinfunction "1_1") (pintype "unspecified"))
      (node (ref "R44") (pin "2") (pinfunction "2_2") (pintype "input"))
      (node (ref "TP3") (pin "1") (pinfunction "1_1") (pintype "unspecified"))
      (node (ref "U1") (pin "5") (pinfunction "OUT_5") (pintype "unspecified"))
    )
    (net (code "2") (name "+3.3V") (class "Default")
      (node (ref "C10") (pin "2") (pinfunction "2_2") (pintype "input"))
      (node (ref "C11") (pin "2") (pinfunction "2_2") (pintype "input"))
      (node (ref "C14") (pin "2") (pinfunction "2_2") (pintype "input"))
      (node (ref "C15") (pin "2") (pinfunction "2_2") (pintype "unspecified"))
      (node (ref "C16") (pin "2") (pinfunction "2_2") (pintype "input"))
      (node (ref "C17") (pin "1") (pinfunction "1_1") (pintype "unspecified"))
      (node (ref "C19") (pin "2") (pinfunction "2_2") (pintype "unspecified"))
      (node (ref "C28") (pin "2") (pinfunction "2_2") (pintype "input"))
      (node (ref "C29") (pin "2") (pinfunction "2_2") (pintype "unspecified"))
      (node (ref "C35") (pin "1") (pinfunction "1_1") (pintype "input"))
      (node (ref "C75") (pin "2") (pinfunction "2_2") (pintype "input"))
      (node (ref "C8") (pin "2") (pinfunction "2_2") (pintype "input"))
      (node (ref "D15") (pin "1") (pinfunction "K_1") (pintype "unspecified"))
      (node (ref "D2") (pin "1") (pinfunction "K_1") (pintype "unspecified"))
      (node (ref "D3") (pin "1") (pinfunction "K_1") (pintype "unspecified"))
      (node (ref "D9") (pin "1") (pinfunction "K_1") (pintype "unspecified"))
      (node (ref "H2") (pin "1") (pinfunction "1_1") (pintype "input"))
      (node (ref "L1") (pin "2") (pinfunction "2_2") (pintype "unspecified"))
      (node (ref "LED3") (pin "2") (pinfunction "COM+_2") (pintype "unspecified"))
      (node (ref "LED4") (pin "2") (pinfunction "A_2") (pintype "unspecified"))
      (node (ref "R10") (pin "1") (pinfunction "1_1") (pintype "input"))
      (node (ref "R11") (pin "3") (pinfunction "3_3") (pintype "input"))
      (node (ref "R2") (pin "1") (pinfunction "1_1") (pintype "input"))
      (node (ref "R38") (pin "1") (pinfunction "1_1") (pintype "input"))
      (node (ref "R7") (pin "2") (pinfunction "2_2") (pintype "input"))
      (node (ref "R81") (pin "1") (pinfunction "1_1") (pintype "input"))
      (node (ref "R9") (pin "1") (pinfunction "1_1") (pintype "input"))
      (node (ref "TP5") (pin "1") (pinfunction "1_1") (pintype "unspecified"))
      (node (ref "U12") (pin "2") (pinfunction "A_2") (pintype "unspecified"))
      (node (ref "U23") (pin "10") (pinfunction "VCC_10") (pintype "unspecified"))
      (node (ref "U24") (pin "8") (pinfunction "+VS_8") (pintype "unspecified"))
      (node (ref "U25") (pin "8") (pinfunction "+VS_8") (pintype "unspecified"))
      (node (ref "U26") (pin "5") (pinfunction "VCC_5") (pintype "unspecified"))
      (node (ref "U26") (pin "8") (pinfunction "V3_8") (pintype "unspecified"))
      (node (ref "U3") (pin "1") (pinfunction "VBAT_1") (pintype "unspecified"))
      (node (ref "U3") (pin "16") (pinfunction "VDD_16") (pintype "unspecified"))
      (node (ref "U3") (pin "28") (pinfunction "VREF+_28") (pintype "unspecified"))
      (node (ref "U3") (pin "29") (pinfunction "VDDA_29") (pintype "unspecified"))
      (node (ref "U3") (pin "32") (pinfunction "VDD_32") (pintype "unspecified"))
      (node (ref "U3") (pin "48") (pinfunction "VDD_48") (pintype "unspecified"))
      (node (ref "U3") (pin "64") (pinfunction "VDD_64") (pintype "unspecified"))
    )
    (net (code "3") (name "+5V") (class "Default")
      (node (ref "C12") (pin "2") (pinfunction "2_2") (pintype "unspecified"))
      (node (ref "C2") (pin "2") (pinfunction "2_2") (pintype "input"))
      (node (ref "C22") (pin "2") (pinfunction "2_2") (pintype "unspecified"))
      (node (ref "C9") (pin "2") (pinfunction "2_2") (pintype "input"))
      (node (ref "L2") (pin "1") (pinfunction "1_1") (pintype "unspecified"))
      (node (ref "R18") (pin "2") (pinfunction "2_2") (pintype "input"))
      (node (ref "R35") (pin "1") (pinfunction "1_1") (pintype "input"))
      (node (ref "TP2") (pin "1") (pinfunction "1_1") (pintype "unspecified"))
      (node (ref "TP4") (pin "1") (pinfunction "1_1") (pintype "unspecified"))
      (node (ref "U1") (pin "1") (pinfunction "IN_1") (pintype "unspecified"))
      (node (ref "U1") (pin "3") (pinfunction "EN_3") (pintype "unspecified"))
    )
    (net (code "4") (name "+12V") (class "Default")
      (node (ref "C1") (pin "2") (pinfunction "2_2") (pintype "unspecified"))
      (node (ref "C20") (pin "2") (pinfunction "2_2") (pintype "input"))
      (node (ref "C21") (pin "2") (pinfunction "2_2") (pintype "input"))
      (node (ref "C41") (pin "2") (pinfunction "2_2") (pintype "input"))
      (node (ref "C42") (pin "2") (pinfunction "2_2") (pintype "input"))
      (node (ref "C5") (pin "2") (pinfunction "2_2") (pintype "unspecified"))
      (node (ref "C6") (pin "2") (pinfunction "2_2") (pintype "unspecified"))
      (node (ref "D1") (pin "2") (pinfunction "A_2") (pintype "unspecified"))
      (node (ref "D4") (pin "2") (pinfunction "A_2") (pintype "unspecified"))
      (node (ref "D5") (pin "2") (pinfunction "A_2") (pintype "unspecified"))
      (node (ref "D7") (pin "2") (pinfunction "A_2") (pintype "unspecified"))
      (node (ref "L3") (pin "1") (pinfunction "1_1") (pintype "unspecified"))
      (node (ref "R1") (pin "1") (pinfunction "1_1") (pintype "input"))
      (node (ref "U14") (pin "1") (pinfunction "VCC_1") (pintype "unspecified"))
      (node (ref "U15") (pin "1") (pinfunction "VCC_1") (pintype "unspecified"))
      (node (ref "U16") (pin "1") (pinfunction "VCC_1") (pintype "unspecified"))
      (node (ref "U17") (pin "1") (pinfunction "VCC_1") (pintype "unspecified"))
      (node (ref "U2") (pin "4") (pinfunction "EN_4") (pintype "unspecified"))
      (node (ref "U2") (pin "5") (pinfunction "IN_5") (pintype "unspecified"))
    )
    (net (code "5") (name "/A") (class "Default")
      (node (ref "CN2") (pin "2") (pinfunction "2_2") (pintype "unspecified"))
      (node (ref "Q1") (pin "1") (pinfunction "S_1") (pintype "unspecified"))
      (node (ref "Q1") (pin "2") (pinfunction "S_2") (pintype "unspecified"))
      (node (ref "Q1") (pin "3") (pinfunction "S_3") (pintype "unspecified"))
      (node (ref "Q5") (pin "5") (pinfunction "D_5") (pintype "unspecified"))
      (node (ref "Q5") (pin "6") (pinfunction "D_6") (pintype "unspecified"))
      (node (ref "Q5") (pin "7") (pinfunction "D_7") (pintype "unspecified"))
      (node (ref "Q5") (pin "8") (pinfunction "D_8") (pintype "unspecified"))
      (node (ref "R12") (pin "1") (pinfunction "1_1") (pintype "input"))
      (node (ref "R33") (pin "1") (pinfunction "1_1") (pintype "input"))
      (node (ref "U14") (pin "6") (pinfunction "VS_6") (pintype "unspecified"))
      (node (ref "U5") (pin "1") (pinfunction "1_1") (pintype "unspecified"))
    )
    (net (code "6") (name "/ADC_IN") (class "Default")
      (node (ref "R11") (pin "2") (pinfunction "2_2") (pintype "input"))
      (node (ref "U3") (pin "26") (pinfunction "PB2_26") (pintype "unspecified"))
    )
    (net (code "7") (name "/B") (class "Default")
      (node (ref "CN2") (pin "1") (pinfunction "1_1") (pintype "unspecified"))
      (node (ref "Q2") (pin "1") (pinfunction "S_1") (pintype "unspecified"))
      (node (ref "Q2") (pin "2") (pinfunction "S_2") (pintype "unspecified"))
      (node (ref "Q2") (pin "3") (pinfunction "S_3") (pintype "unspecified"))
      (node (ref "Q6") (pin "5") (pinfunction "D_5") (pintype "unspecified"))
      (node (ref "Q6") (pin "6") (pinfunction "D_6") (pintype "unspecified"))
      (node (ref "Q6") (pin "7") (pinfunction "D_7") (pintype "unspecified"))
      (node (ref "Q6") (pin "8") (pinfunction "D_8") (pintype "unspecified"))
      (node (ref "R19") (pin "1") (pinfunction "1_1") (pintype "input"))
      (node (ref "R32") (pin "1") (pinfunction "1_1") (pintype "input"))
      (node (ref "U15") (pin "6") (pinfunction "VS_6") (pintype "unspecified"))
      (node (ref "U18") (pin "1") (pinfunction "1_1") (pintype "unspecified"))
    )
    (net (code "8") (name "/BEMF_A") (class "Default")
      (node (ref "C24") (pin "1") (pinfunction "1_1") (pintype "input"))
      (node (ref "D2") (pin "2") (pinfunction "A_2") (pintype "unspecified"))
      (node (ref "R12") (pin "2") (pinfunction "2_2") (pintype "input"))
      (node (ref "R14") (pin "2") (pinfunction "2_2") (pintype "input"))
      (node (ref "U3") (pin "22") (pinfunction "PC4_22") (pintype "unspecified"))
    )
    (net (code "9") (name "/BEMF_B") (class "Default")
      (node (ref "C26") (pin "1") (pinfunction "1_1") (pintype "input"))
      (node (ref "D3") (pin "2") (pinfunction "A_2") (pintype "unspecified"))
      (node (ref "R15") (pin "2") (pinfunction "2_2") (pintype "input"))
      (node (ref "R19") (pin "2") (pinfunction "2_2") (pintype "input"))
      (node (ref "U3") (pin "21") (pinfunction "PA7_21") (pintype "unspecified"))
    )
    (net (code "10") (name "/BEMF_C") (class "Default")
      (node (ref "C27") (pin "1") (pinfunction "1_1") (pintype "input"))
      (node (ref "D9") (pin "2") (pinfunction "A_2") (pintype "unspecified"))
      (node (ref "R21") (pin "2") (pinfunction "2_2") (pintype "input"))
      (node (ref "R22") (pin "2") (pinfunction "2_2") (pintype "input"))
      (node (ref "U3") (pin "19") (pinfunction "PA5_19") (pintype "unspecified"))
    )
    (net (code "11") (name "/BOOT0") (class "Default")
      (node (ref "R13") (pin "2") (pinfunction "2_2") (pintype "input"))
      (node (ref "U3") (pin "61") (pinfunction "PB8-BOOT0_61") (pintype "unspecified"))
    )
    (net (code "12") (name "/C") (class "Default")
      (node (ref "CN3") (pin "2") (pinfunction "2_2") (pintype "unspecified"))
      (node (ref "Q3") (pin "1") (pinfunction "S_1") (pintype "unspecified"))
      (node (ref "Q3") (pin "2") (pinfunction "S_2") (pintype "unspecified"))
      (node (ref "Q3") (pin "3") (pinfunction "S_3") (pintype "unspecified"))
      (node (ref "Q7") (pin "5") (pinfunction "D_5") (pintype "unspecified"))
      (node (ref "Q7") (pin "6") (pinfunction "D_6") (pintype "unspecified"))
      (node (ref "Q7") (pin "7") (pinfunction "D_7") (pintype "unspecified"))
      (node (ref "Q7") (pin "8") (pinfunction "D_8") (pintype "unspecified"))
      (node (ref "R22") (pin "1") (pinfunction "1_1") (pintype "input"))
      (node (ref "R27") (pin "1") (pinfunction "1_1") (pintype "input"))
      (node (ref "U10") (pin "1") (pinfunction "1_1") (pintype "unspecified"))
      (node (ref "U16") (pin "6") (pinfunction "VS_6") (pintype "unspecified"))
    )
    (net (code "13") (name "/D") (class "Default")
      (node (ref "CN3") (pin "1") (pinfunction "1_1") (pintype "unspecified"))
      (node (ref "Q4") (pin "1") (pinfunction "S_1") (pintype "unspecified"))
      (node (ref "Q4") (pin "2") (pinfunction "S_2") (pintype "unspecified"))
      (node (ref "Q4") (pin "3") (pinfunction "S_3") (pintype "unspecified"))
      (node (ref "Q8") (pin "5") (pinfunction "D_5") (pintype "unspecified"))
      (node (ref "Q8") (pin "6") (pinfunction "D_6") (pintype "unspecified"))
      (node (ref "Q8") (pin "7") (pinfunction "D_7") (pintype "unspecified"))
      (node (ref "Q8") (pin "8") (pinfunction "D_8") (pintype "unspecified"))
      (node (ref "R37") (pin "1") (pinfunction "1_1") (pintype "input"))
      (node (ref "U17") (pin "6") (pinfunction "VS_6") (pintype "unspecified"))
      (node (ref "U4") (pin "1") (pinfunction "1_1") (pintype "unspecified"))
    )
    (net (code "14") (name "/D+") (class "Default")
      (node (ref "U26") (pin "1") (pinfunction "UD+_1") (pintype "unspecified"))
      (node (ref "USB1") (pin "A6") (pinfunction "DP1_A6") (pintype "unspecified"))
      (node (ref "USB1") (pin "B6") (pinfunction "DP2_B6") (pintype "unspecified"))
    )
    (net (code "15") (name "/D-") (class "Default")
      (node (ref "U26") (pin "2") (pinfunction "UD-_2") (pintype "unspecified"))
      (node (ref "USB1") (pin "A7") (pinfunction "DN1_A7") (pintype "unspecified"))
      (node (ref "USB1") (pin "B7") (pinfunction "DN2_B7") (pintype "unspecified"))
    )
    (net (code "16") (name "/IA") (class "Default")
      (node (ref "C25") (pin "2") (pinfunction "2_2") (pintype "input"))
      (node (ref "R57") (pin "2") (pinfunction "2_2") (pintype "input"))
      (node (ref "U3") (pin "20") (pinfunction "PA6_20") (pintype "unspecified"))
    )
    (net (code "17") (name "/IC") (class "Default")
      (node (ref "C34") (pin "2") (pinfunction "2_2") (pintype "input"))
      (node (ref "R65") (pin "2") (pinfunction "2_2") (pintype "input"))
      (node (ref "U3") (pin "18") (pinfunction "PA4_18") (pintype "unspecified"))
    )
    (net (code "18") (name "/I_A") (class "Default")
      (node (ref "Q5") (pin "1") (pinfunction "S_1") (pintype "unspecified"))
      (node (ref "Q5") (pin "2") (pinfunction "S_2") (pintype "unspecified"))
      (node (ref "Q5") (pin "3") (pinfunction "S_3") (pintype "unspecified"))
      (node (ref "R28") (pin "2") (pinfunction "2_2") (pintype "unspecified"))
      (node (ref "R34") (pin "1") (pinfunction "1_1") (pintype "input"))
      (node (ref "R63") (pin "1") (pinfunction "1_1") (pintype "unspecified"))
    )
    (net (code "19") (name "/I_C") (class "Default")
      (node (ref "Q7") (pin "1") (pinfunction "S_1") (pintype "unspecified"))
      (node (ref "Q7") (pin "2") (pinfunction "S_2") (pintype "unspecified"))
      (node (ref "Q7") (pin "3") (pinfunction "S_3") (pintype "unspecified"))
      (node (ref "R26") (pin "1") (pinfunction "1_1") (pintype "input"))
      (node (ref "R29") (pin "2") (pinfunction "2_2") (pintype "unspecified"))
      (node (ref "R47") (pin "2") (pinfunction "2_2") (pintype "unspecified"))
    )
    (net (code "20") (name "/KEY1") (class "Default")
      (node (ref "R9") (pin "2") (pinfunction "2_2") (pintype "input"))
      (node (ref "SW2") (pin "1") (pinfunction "1_1") (pintype "unspecified"))
      (node (ref "U3") (pin "41") (pinfunction "PC9_41") (pintype "unspecified"))
    )
    (net (code "21") (name "/KEY2") (class "Default")
      (node (ref "R10") (pin "2") (pinfunction "2_2") (pintype "input"))
      (node (ref "SW3") (pin "1") (pinfunction "1_1") (pintype "unspecified"))
      (node (ref "U3") (pin "34") (pinfunction "PB12_34") (pintype "unspecified"))
    )
    (net (code "22") (name "/LCD_RS") (class "Default")
      (node (ref "U23") (pin "5") (pinfunction "RS_5") (pintype "unspecified"))
      (node (ref "U3") (pin "55") (pinfunction "PD2_55") (pintype "unspecified"))
    )
    (net (code "23") (name "/LCD_RST") (class "Default")
      (node (ref "U23") (pin "6") (pinfunction "RES_6") (pintype "unspecified"))
      (node (ref "U3") (pin "53") (pinfunction "PC11_53") (pintype "unspecified"))
    )
    (net (code "24") (name "/LED_B") (class "Default")
      (node (ref "R23") (pin "2") (pinfunction "2_2") (pintype "input"))
      (node (ref "U3") (pin "2") (pinfunction "PC13_2") (pintype "unspecified"))
    )
    (net (code "25") (name "/LED_G") (class "Default")
      (node (ref "R20") (pin "2") (pinfunction "2_2") (pintype "input"))
      (node (ref "U3") (pin "3") (pinfunction "PC14-OSC32_IN_3") (pintype "unspecified"))
    )
    (net (code "26") (name "/LED_R") (class "Default")
      (node (ref "R17") (pin "1") (pinfunction "1_1") (pintype "input"))
      (node (ref "U3") (pin "4") (pinfunction "PC15-OSC32_OUT_4") (pintype "unspecified"))
    )
    (net (code "27") (name "/MOS_AH") (class "Default")
      (node (ref "D19") (pin "2") (pinfunction "A_2") (pintype "unspecified"))
      (node (ref "Q1") (pin "4") (pinfunction "G_4") (pintype "unspecified"))
      (node (ref "R33") (pin "2") (pinfunction "2_2") (pintype "input"))
      (node (ref "R51") (pin "2") (pinfunction "2_2") (pintype "unspecified"))
    )
    (net (code "28") (name "/MOS_AL") (class "Default")
      (node (ref "D20") (pin "2") (pinfunction "A_2") (pintype "unspecified"))
      (node (ref "Q5") (pin "4") (pinfunction "G_4") (pintype "unspecified"))
      (node (ref "R34") (pin "2") (pinfunction "2_2") (pintype "input"))
      (node (ref "R52") (pin "2") (pinfunction "2_2") (pintype "unspecified"))
    )
    (net (code "29") (name "/MOS_BH") (class "Default")
      (node (ref "D22") (pin "2") (pinfunction "A_2") (pintype "unspecified"))
      (node (ref "Q2") (pin "4") (pinfunction "G_4") (pintype "unspecified"))
      (node (ref "R32") (pin "2") (pinfunction "2_2") (pintype "input"))
      (node (ref "R49") (pin "2") (pinfunction "2_2") (pintype "unspecified"))
    )
    (net (code "30") (name "/MOS_BL") (class "Default")
      (node (ref "D21") (pin "2") (pinfunction "A_2") (pintype "unspecified"))
      (node (ref "Q6") (pin "4") (pinfunction "G_4") (pintype "unspecified"))
      (node (ref "R31") (pin "2") (pinfunction "2_2") (pintype "input"))
      (node (ref "R50") (pin "2") (pinfunction "2_2") (pintype "unspecified"))
    )
    (net (code "31") (name "/MOS_CH") (class "Default")
      (node (ref "D24") (pin "2") (pinfunction "A_2") (pintype "unspecified"))
      (node (ref "Q3") (pin "4") (pinfunction "G_4") (pintype "unspecified"))
      (node (ref "R27") (pin "2") (pinfunction "2_2") (pintype "input"))
      (node (ref "R46") (pin "2") (pinfunction "2_2") (pintype "unspecified"))
    )
    (net (code "32") (name "/MOS_CL") (class "Default")
      (node (ref "D23") (pin "2") (pinfunction "A_2") (pintype "unspecified"))
      (node (ref "Q7") (pin "4") (pinfunction "G_4") (pintype "unspecified"))
      (node (ref "R26") (pin "2") (pinfunction "2_2") (pintype "input"))
      (node (ref "R48") (pin "2") (pinfunction "2_2") (pintype "unspecified"))
    )
    (net (code "33") (name "/MOS_DH") (class "Default")
      (node (ref "D28") (pin "2") (pinfunction "A_2") (pintype "unspecified"))
      (node (ref "Q4") (pin "4") (pinfunction "G_4") (pintype "unspecified"))
      (node (ref "R30") (pin "2") (pinfunction "2_2") (pintype "unspecified"))
      (node (ref "R37") (pin "2") (pinfunction "2_2") (pintype "input"))
    )
    (net (code "34") (name "/MOS_DL") (class "Default")
      (node (ref "D25") (pin "2") (pinfunction "A_2") (pintype "unspecified"))
      (node (ref "Q8") (pin "4") (pinfunction "G_4") (pintype "unspecified"))
      (node (ref "R40") (pin "2") (pinfunction "2_2") (pintype "input"))
      (node (ref "R45") (pin "2") (pinfunction "2_2") (pintype "unspecified"))
    )
    (net (code "35") (name "/OSC_IN") (class "Default")
      (node (ref "C7") (pin "2") (pinfunction "2_2") (pintype "input"))
      (node (ref "U3") (pin "5") (pinfunction "PF0-OSC_IN_5") (pintype "unspecified"))
      (node (ref "X1") (pin "3") (pinfunction "3_3") (pintype "input"))
    )
    (net (code "36") (name "/OSC_OUT") (class "Default")
      (node (ref "C4") (pin "1") (pinfunction "1_1") (pintype "input"))
      (node (ref "U3") (pin "6") (pinfunction "PF1-OSC_OUT_6") (pintype "unspecified"))
      (node (ref "X1") (pin "1") (pinfunction "1_1") (pintype "input"))
    )
    (net (code "37") (name "/PWMA") (class "Default")
      (node (ref "U14") (pin "2") (pinfunction "IN_2") (pintype "unspecified"))
      (node (ref "U3") (pin "8") (pinfunction "PC0_8") (pintype "unspecified"))
    )
    (net (code "38") (name "/PWMB") (class "Default")
      (node (ref "U15") (pin "2") (pinfunction "IN_2") (pintype "unspecified"))
      (node (ref "U3") (pin "9") (pinfunction "PC1_9") (pintype "unspecified"))
    )
    (net (code "39") (name "/PWMC") (class "Default")
      (node (ref "U16") (pin "2") (pinfunction "IN_2") (pintype "unspecified"))
      (node (ref "U3") (pin "10") (pinfunction "PC2_10") (pintype "unspecified"))
    )
    (net (code "40") (name "/PWMD") (class "Default")
      (node (ref "U17") (pin "2") (pinfunction "IN_2") (pintype "unspecified"))
      (node (ref "U3") (pin "11") (pinfunction "PC3_11") (pintype "unspecified"))
    )
    (net (code "41") (name "/RST") (class "Default")
      (node (ref "C13") (pin "1") (pinfunction "1_1") (pintype "input"))
      (node (ref "R7") (pin "1") (pinfunction "1_1") (pintype "input"))
      (node (ref "SW1") (pin "3") (pinfunction "3_3") (pintype "unspecified"))
      (node (ref "U3") (pin "7") (pinfunction "PG10-NRST_7") (pintype "unspecified"))
    )
    (net (code "42") (name "/SD1") (class "Default")
      (node (ref "U14") (pin "3") (pinfunction "SD#_3") (pintype "unspecified"))
      (node (ref "U3") (pin "24") (pinfunction "PB0_24") (pintype "unspecified"))
    )
    (net (code "43") (name "/SD2") (class "Default")
      (node (ref "U15") (pin "3") (pinfunction "SD#_3") (pintype "unspecified"))
      (node (ref "U3") (pin "13") (pinfunction "PA1_13") (pintype "unspecified"))
    )
    (net (code "44") (name "/SD3") (class "Default")
      (node (ref "U16") (pin "3") (pinfunction "SD#_3") (pintype "unspecified"))
      (node (ref "U3") (pin "14") (pinfunction "PA2_14") (pintype "unspecified"))
    )
    (net (code "45") (name "/SD4") (class "Default")
      (node (ref "U17") (pin "3") (pinfunction "SD#_3") (pintype "unspecified"))
      (node (ref "U3") (pin "12") (pinfunction "PA0_12") (pintype "unspecified"))
    )
    (net (code "46") (name "/SPI1_CS") (class "Default")
      (node (ref "U3") (pin "62") (pinfunction "PB9_62") (pintype "unspecified"))
      (node (ref "U7") (pin "4") (pinfunction "4_4") (pintype "unspecified"))
    )
    (net (code "47") (name "/SPI1_MISO") (class "Default")
      (node (ref "U3") (pin "57") (pinfunction "PB4_57") (pintype "unspecified"))
      (node (ref "U7") (pin "2") (pinfunction "2_2") (pintype "unspecified"))
    )
    (net (code "48") (name "/SPI1_MOSI") (class "Default")
      (node (ref "U3") (pin "58") (pinfunction "PB5_58") (pintype "unspecified"))
      (node (ref "U7") (pin "5") (pinfunction "5_5") (pintype "unspecified"))
    )
    (net (code "49") (name "/SPI1_SCK") (class "Default")
      (node (ref "U3") (pin "56") (pinfunction "PB3_56") (pintype "unspecified"))
      (node (ref "U7") (pin "3") (pinfunction "3_3") (pintype "unspecified"))
    )
    (net (code "50") (name "/SPI3_CS") (class "Default")
      (node (ref "U23") (pin "7") (pinfunction "CS_7") (pintype "unspecified"))
      (node (ref "U3") (pin "51") (pinfunction "PA15_51") (pintype "unspecified"))
    )
    (net (code "51") (name "/SPI3_MOSI") (class "Default")
      (node (ref "U23") (pin "3") (pinfunction "SDA_3") (pintype "unspecified"))
      (node (ref "U3") (pin "54") (pinfunction "PC12_54") (pintype "unspecified"))
    )
    (net (code "52") (name "/SPI3_SCK") (class "Default")
      (node (ref "U23") (pin "4") (pinfunction "SCL_4") (pintype "unspecified"))
      (node (ref "U3") (pin "52") (pinfunction "PC10_52") (pintype "unspecified"))
    )
    (net (code "53") (name "/SWCLK") (class "Default")
      (node (ref "H2") (pin "3") (pinfunction "3_3") (pintype "input"))
      (node (ref "U3") (pin "50") (pinfunction "PA14_50") (pintype "unspecified"))
    )
    (net (code "54") (name "/SWDIO") (class "Default")
      (node (ref "H2") (pin "2") (pinfunction "2_2") (pintype "input"))
      (node (ref "U3") (pin "49") (pinfunction "PA13_49") (pintype "unspecified"))
    )
    (net (code "55") (name "/TEMP") (class "Default")
      (node (ref "R36") (pin "2") (pinfunction "2_2") (pintype "input"))
      (node (ref "R38") (pin "2") (pinfunction "2_2") (pintype "input"))
      (node (ref "U3") (pin "37") (pinfunction "PB15_37") (pintype "unspecified"))
    )
    (net (code "56") (name "/USART1_RX") (class "Default")
      (node (ref "R66") (pin "1") (pinfunction "1_1") (pintype "input"))
      (node (ref "U26") (pin "6") (pinfunction "TXD_6") (pintype "unspecified"))
      (node (ref "U3") (pin "60") (pinfunction "PB7_60") (pintype "unspecified"))
    )
    (net (code "57") (name "/USART1_TX") (class "Default")
      (node (ref "R68") (pin "1") (pinfunction "1_1") (pintype "input"))
      (node (ref "U26") (pin "7") (pinfunction "RXD_7") (pintype "unspecified"))
      (node (ref "U3") (pin "59") (pinfunction "PB6_59") (pintype "unspecified"))
    )
    (net (code "58") (name "/USART3_RX") (class "Default")
      (node (ref "H2") (pin "5") (pinfunction "5_5") (pintype "input"))
      (node (ref "U3") (pin "33") (pinfunction "PB11_33") (pintype "unspecified"))
    )
    (net (code "59") (name "/USART3_TX") (class "Default")
      (node (ref "H2") (pin "6") (pinfunction "6_6") (pintype "input"))
      (node (ref "U3") (pin "30") (pinfunction "PB10_30") (pintype "unspecified"))
    )
    (net (code "60") (name "/V_BUS") (class "Default")
      (node (ref "C77") (pin "1") (pinfunction "1_1") (pintype "input"))
      (node (ref "R88") (pin "2") (pinfunction "2_2") (pintype "input"))
      (node (ref "U3") (pin "23") (pinfunction "PC5_23") (pintype "unspecified"))
    )
    (net (code "61") (name "DCBUS") (class "Default")
      (node (ref "CN1") (pin "1") (pinfunction "1_1") (pintype "unspecified"))
      (node (ref "D11") (pin "2") (pinfunction "2_2") (pintype "unspecified"))
      (node (ref "Q1") (pin "5") (pinfunction "D_5") (pintype "unspecified"))
      (node (ref "Q1") (pin "6") (pinfunction "D_6") (pintype "unspecified"))
      (node (ref "Q1") (pin "7") (pinfunction "D_7") (pintype "unspecified"))
      (node (ref "Q1") (pin "8") (pinfunction "D_8") (pintype "unspecified"))
      (node (ref "Q2") (pin "5") (pinfunction "D_5") (pintype "unspecified"))
      (node (ref "Q2") (pin "6") (pinfunction "D_6") (pintype "unspecified"))
      (node (ref "Q2") (pin "7") (pinfunction "D_7") (pintype "unspecified"))
      (node (ref "Q2") (pin "8") (pinfunction "D_8") (pintype "unspecified"))
      (node (ref "Q3") (pin "5") (pinfunction "D_5") (pintype "unspecified"))
      (node (ref "Q3") (pin "6") (pinfunction "D_6") (pintype "unspecified"))
      (node (ref "Q3") (pin "7") (pinfunction "D_7") (pintype "unspecified"))
      (node (ref "Q3") (pin "8") (pinfunction "D_8") (pintype "unspecified"))
      (node (ref "Q4") (pin "5") (pinfunction "D_5") (pintype "unspecified"))
      (node (ref "Q4") (pin "6") (pinfunction "D_6") (pintype "unspecified"))
      (node (ref "Q4") (pin "7") (pinfunction "D_7") (pintype "unspecified"))
      (node (ref "Q4") (pin "8") (pinfunction "D_8") (pintype "unspecified"))
      (node (ref "R83") (pin "2") (pinfunction "2_2") (pintype "input"))
      (node (ref "U11") (pin "1") (pinfunction "1_1") (pintype "input"))
      (node (ref "U13") (pin "2") (pinfunction "A_2") (pintype "unspecified"))
      (node (ref "U8") (pin "1") (pinfunction "1_1") (pintype "input"))
    )
    (net (code "62") (name "DGND") (class "Default")
      (node (ref "C1") (pin "1") (pinfunction "1_1") (pintype "unspecified"))
      (node (ref "C10") (pin "1") (pinfunction "1_1") (pintype "input"))
      (node (ref "C11") (pin "1") (pinfunction "1_1") (pintype "input"))
      (node (ref "C12") (pin "1") (pinfunction "1_1") (pintype "unspecified"))
      (node (ref "C13") (pin "2") (pinfunction "2_2") (pintype "input"))
      (node (ref "C14") (pin "1") (pinfunction "1_1") (pintype "input"))
      (node (ref "C15") (pin "1") (pinfunction "1_1") (pintype "unspecified"))
      (node (ref "C16") (pin "1") (pinfunction "1_1") (pintype "input"))
      (node (ref "C17") (pin "2") (pinfunction "2_2") (pintype "unspecified"))
      (node (ref "C18") (pin "1") (pinfunction "1_1") (pintype "input"))
      (node (ref "C19") (pin "1") (pinfunction "1_1") (pintype "unspecified"))
      (node (ref "C2") (pin "1") (pinfunction "1_1") (pintype "input"))
      (node (ref "C20") (pin "1") (pinfunction "1_1") (pintype "input"))
      (node (ref "C21") (pin "1") (pinfunction "1_1") (pintype "input"))
      (node (ref "C22") (pin "1") (pinfunction "1_1") (pintype "unspecified"))
      (node (ref "C23") (pin "2") (pinfunction "2_2") (pintype "unspecified"))
      (node (ref "C24") (pin "2") (pinfunction "2_2") (pintype "input"))
      (node (ref "C25") (pin "1") (pinfunction "1_1") (pintype "input"))
      (node (ref "C26") (pin "2") (pinfunction "2_2") (pintype "input"))
      (node (ref "C27") (pin "2") (pinfunction "2_2") (pintype "input"))
      (node (ref "C28") (pin "1") (pinfunction "1_1") (pintype "input"))
      (node (ref "C29") (pin "1") (pinfunction "1_1") (pintype "unspecified"))
      (node (ref "C30") (pin "2") (pinfunction "2_2") (pintype "unspecified"))
      (node (ref "C34") (pin "1") (pinfunction "1_1") (pintype "input"))
      (node (ref "C35") (pin "2") (pinfunction "2_2") (pintype "input"))
      (node (ref "C4") (pin "2") (pinfunction "2_2") (pintype "input"))
      (node (ref "C41") (pin "1") (pinfunction "1_1") (pintype "input"))
      (node (ref "C42") (pin "1") (pinfunction "1_1") (pintype "input"))
      (node (ref "C5") (pin "1") (pinfunction "1_1") (pintype "unspecified"))
      (node (ref "C6") (pin "1") (pinfunction "1_1") (pintype "unspecified"))
      (node (ref "C7") (pin "1") (pinfunction "1_1") (pintype "input"))
      (node (ref "C71") (pin "1") (pinfunction "1_1") (pintype "input"))
      (node (ref "C75") (pin "1") (pinfunction "1_1") (pintype "input"))
      (node (ref "C76") (pin "1") (pinfunction "1_1") (pintype "input"))
      (node (ref "C77") (pin "2") (pinfunction "2_2") (pintype "input"))
      (node (ref "C8") (pin "1") (pinfunction "1_1") (pintype "input"))
      (node (ref "C9") (pin "1") (pinfunction "1_1") (pintype "input"))
      (node (ref "D11") (pin "1") (pinfunction "1_1") (pintype "unspecified"))
      (node (ref "D8") (pin "1") (pinfunction "A_1") (pintype "unspecified"))
      (node (ref "H2") (pin "4") (pinfunction "4_4") (pintype "input"))
      (node (ref "R11") (pin "1") (pinfunction "1_1") (pintype "input"))
      (node (ref "R13") (pin "1") (pinfunction "1_1") (pintype "input"))
      (node (ref "R14") (pin "1") (pinfunction "1_1") (pintype "input"))
      (node (ref "R15") (pin "1") (pinfunction "1_1") (pintype "input"))
      (node (ref "R21") (pin "1") (pinfunction "1_1") (pintype "input"))
      (node (ref "R3") (pin "2") (pinfunction "2_2") (pintype "input"))
      (node (ref "R36") (pin "1") (pinfunction "1_1") (pintype "input"))
      (node (ref "R4") (pin "1") (pinfunction "1_1") (pintype "input"))
      (node (ref "R5") (pin "2") (pinfunction "2_2") (pintype "input"))
      (node (ref "R56") (pin "1") (pinfunction "1_1") (pintype "input"))
      (node (ref "SW1") (pin "2") (pinfunction "2_2") (pintype "unspecified"))
      (node (ref "SW2") (pin "4") (pinfunction "4_4") (pintype "unspecified"))
      (node (ref "SW3") (pin "4") (pinfunction "4_4") (pintype "unspecified"))
      (node (ref "U1") (pin "2") (pinfunction "GND_2") (pintype "unspecified"))
      (node (ref "U11") (pin "2") (pinfunction "2_2") (pintype "input"))
      (node (ref "U14") (pin "4") (pinfunction "GND_4") (pintype "unspecified"))
      (node (ref "U15") (pin "4") (pinfunction "GND_4") (pintype "unspecified"))
      (node (ref "U16") (pin "4") (pinfunction "GND_4") (pintype "unspecified"))
      (node (ref "U17") (pin "4") (pinfunction "GND_4") (pintype "unspecified"))
      (node (ref "U2") (pin "2") (pinfunction "GND_2") (pintype "unspecified"))
      (node (ref "U23") (pin "11") (pinfunction "LEDK_11") (pintype "unspecified"))
      (node (ref "U23") (pin "13") (pinfunction "GND_13") (pintype "unspecified"))
      (node (ref "U23") (pin "8") (pinfunction "GND_8") (pintype "unspecified"))
      (node (ref "U24") (pin "4") (pinfunction "-VS_4") (pintype "unspecified"))
      (node (ref "U25") (pin "4") (pinfunction "-VS_4") (pintype "unspecified"))
      (node (ref "U26") (pin "3") (pinfunction "GND_3") (pintype "unspecified"))
      (node (ref "U3") (pin "15") (pinfunction "VSS_15") (pintype "unspecified"))
      (node (ref "U3") (pin "27") (pinfunction "VSSA_27") (pintype "unspecified"))
      (node (ref "U3") (pin "31") (pinfunction "VSS_31") (pintype "unspecified"))
      (node (ref "U3") (pin "47") (pinfunction "VSS_47") (pintype "unspecified"))
      (node (ref "U3") (pin "63") (pinfunction "VSS_63") (pintype "unspecified"))
      (node (ref "U6") (pin "1") (pinfunction "K_1") (pintype "unspecified"))
      (node (ref "U7") (pin "6") (pinfunction "6_6") (pintype "unspecified"))
      (node (ref "U8") (pin "2") (pinfunction "2_2") (pintype "input"))
      (node (ref "U9") (pin "4") (pinfunction "EN_4") (pintype "unspecified"))
      (node (ref "U9") (pin "5") (pinfunction "GND_5") (pintype "unspecified"))
      (node (ref "U9") (pin "6") (pinfunction "GND_6") (pintype "unspecified"))
      (node (ref "U9") (pin "7") (pinfunction "GND_7") (pintype "unspecified"))
      (node (ref "U9") (pin "8") (pinfunction "GND_8") (pintype "unspecified"))
      (node (ref "U9") (pin "9") (pinfunction "9_9") (pintype "unspecified"))
      (node (ref "USB1") (pin "1") (pinfunction "SHELL_1") (pintype "unspecified"))
      (node (ref "USB1") (pin "2") (pinfunction "SHELL_2") (pintype "unspecified"))
      (node (ref "USB1") (pin "3") (pinfunction "SHELL_3") (pintype "unspecified"))
      (node (ref "USB1") (pin "4") (pinfunction "SHELL_4") (pintype "unspecified"))
      (node (ref "USB1") (pin "A1B12") (pinfunction "GND_A1B12") (pintype "unspecified"))
      (node (ref "USB1") (pin "B1A12") (pinfunction "GND_B1A12") (pintype "unspecified"))
      (node (ref "X1") (pin "2") (pinfunction "GND_2") (pintype "input"))
      (node (ref "X1") (pin "4") (pinfunction "GND_4") (pintype "input"))
    )
    (net (code "63") (name "Net-(D1-K)") (class "Default")
      (node (ref "D1") (pin "1") (pinfunction "K_1") (pintype "unspecified"))
      (node (ref "U15") (pin "8") (pinfunction "VB_8") (pintype "unspecified"))
      (node (ref "U18") (pin "2") (pinfunction "2_2") (pintype "unspecified"))
    )
    (net (code "64") (name "Net-(D4-K)") (class "Default")
      (node (ref "D4") (pin "1") (pinfunction "K_1") (pintype "unspecified"))
      (node (ref "U10") (pin "2") (pinfunction "2_2") (pintype "unspecified"))
      (node (ref "U16") (pin "8") (pinfunction "VB_8") (pintype "unspecified"))
    )
    (net (code "65") (name "Net-(D5-K)") (class "Default")
      (node (ref "D5") (pin "1") (pinfunction "K_1") (pintype "unspecified"))
      (node (ref "U17") (pin "8") (pinfunction "VB_8") (pintype "unspecified"))
      (node (ref "U4") (pin "2") (pinfunction "2_2") (pintype "unspecified"))
    )
    (net (code "66") (name "Net-(D7-K)") (class "Default")
      (node (ref "D7") (pin "1") (pinfunction "K_1") (pintype "unspecified"))
      (node (ref "U14") (pin "8") (pinfunction "VB_8") (pintype "unspecified"))
      (node (ref "U5") (pin "2") (pinfunction "2_2") (pintype "unspecified"))
    )
    (net (code "67") (name "Net-(D8-K)") (class "Default")
      (node (ref "D8") (pin "2") (pinfunction "K_2") (pintype "unspecified"))
      (node (ref "L3") (pin "2") (pinfunction "2_2") (pintype "unspecified"))
      (node (ref "U9") (pin "2") (pinfunction "SW_2") (pintype "unspecified"))
    )
    (net (code "68") (name "Net-(D15-A)") (class "Default")
      (node (ref "C30") (pin "1") (pinfunction "1_1") (pintype "unspecified"))
      (node (ref "D15") (pin "2") (pinfunction "A_2") (pintype "unspecified"))
      (node (ref "R56") (pin "2") (pinfunction "2_2") (pintype "input"))
      (node (ref "R83") (pin "1") (pinfunction "1_1") (pintype "input"))
      (node (ref "U24") (pin "3") (pinfunction "+IN1_3") (pintype "unspecified"))
    )
    (net (code "69") (name "Net-(D19-K)") (class "Default")
      (node (ref "D19") (pin "1") (pinfunction "K_1") (pintype "unspecified"))
      (node (ref "R51") (pin "1") (pinfunction "1_1") (pintype "unspecified"))
      (node (ref "U14") (pin "7") (pinfunction "HO_7") (pintype "unspecified"))
    )
    (net (code "70") (name "Net-(D20-K)") (class "Default")
      (node (ref "D20") (pin "1") (pinfunction "K_1") (pintype "unspecified"))
      (node (ref "R52") (pin "1") (pinfunction "1_1") (pintype "unspecified"))
      (node (ref "U14") (pin "5") (pinfunction "LO_5") (pintype "unspecified"))
    )
    (net (code "71") (name "Net-(D21-K)") (class "Default")
      (node (ref "D21") (pin "1") (pinfunction "K_1") (pintype "unspecified"))
      (node (ref "R50") (pin "1") (pinfunction "1_1") (pintype "unspecified"))
      (node (ref "U15") (pin "5") (pinfunction "LO_5") (pintype "unspecified"))
    )
    (net (code "72") (name "Net-(D22-K)") (class "Default")
      (node (ref "D22") (pin "1") (pinfunction "K_1") (pintype "unspecified"))
      (node (ref "R49") (pin "1") (pinfunction "1_1") (pintype "unspecified"))
      (node (ref "U15") (pin "7") (pinfunction "HO_7") (pintype "unspecified"))
    )
    (net (code "73") (name "Net-(D23-K)") (class "Default")
      (node (ref "D23") (pin "1") (pinfunction "K_1") (pintype "unspecified"))
      (node (ref "R48") (pin "1") (pinfunction "1_1") (pintype "unspecified"))
      (node (ref "U16") (pin "5") (pinfunction "LO_5") (pintype "unspecified"))
    )
    (net (code "74") (name "Net-(D24-K)") (class "Default")
      (node (ref "D24") (pin "1") (pinfunction "K_1") (pintype "unspecified"))
      (node (ref "R46") (pin "1") (pinfunction "1_1") (pintype "unspecified"))
      (node (ref "U16") (pin "7") (pinfunction "HO_7") (pintype "unspecified"))
    )
    (net (code "75") (name "Net-(D25-K)") (class "Default")
      (node (ref "D25") (pin "1") (pinfunction "K_1") (pintype "unspecified"))
      (node (ref "R45") (pin "1") (pinfunction "1_1") (pintype "unspecified"))
      (node (ref "U17") (pin "5") (pinfunction "LO_5") (pintype "unspecified"))
    )
    (net (code "76") (name "Net-(D28-K)") (class "Default")
      (node (ref "D28") (pin "1") (pinfunction "K_1") (pintype "unspecified"))
      (node (ref "R30") (pin "1") (pinfunction "1_1") (pintype "unspecified"))
      (node (ref "U17") (pin "7") (pinfunction "HO_7") (pintype "unspecified"))
    )
    (net (code "77") (name "Net-(LED3-B-)") (class "Default")
      (node (ref "LED3") (pin "3") (pinfunction "B-_3") (pintype "unspecified"))
      (node (ref "R23") (pin "1") (pinfunction "1_1") (pintype "input"))
    )
    (net (code "78") (name "Net-(LED3-G-)") (class "Default")
      (node (ref "LED3") (pin "4") (pinfunction "G-_4") (pintype "unspecified"))
      (node (ref "R20") (pin "1") (pinfunction "1_1") (pintype "input"))
    )
    (net (code "79") (name "Net-(LED3-R-)") (class "Default")
      (node (ref "LED3") (pin "1") (pinfunction "R-_1") (pintype "unspecified"))
      (node (ref "R17") (pin "2") (pinfunction "2_2") (pintype "input"))
    )
    (net (code "80") (name "Net-(LED4-K)") (class "Default")
      (node (ref "LED4") (pin "1") (pinfunction "K_1") (pintype "unspecified"))
      (node (ref "R68") (pin "2") (pinfunction "2_2") (pintype "input"))
    )
    (net (code "81") (name "Net-(TP1-Pad1)") (class "Default")
      (node (ref "TP1") (pin "1") (pinfunction "1_1") (pintype "unspecified"))
      (node (ref "U7") (pin "1") (pinfunction "1_1") (pintype "unspecified"))
    )
    (net (code "82") (name "Net-(U2-BS)") (class "Default")
      (node (ref "C3") (pin "1") (pinfunction "1_1") (pintype "input"))
      (node (ref "U2") (pin "1") (pinfunction "BS_1") (pintype "unspecified"))
    )
    (net (code "83") (name "Net-(U2-FB)") (class "Default")
      (node (ref "R18") (pin "1") (pinfunction "1_1") (pintype "input"))
      (node (ref "R5") (pin "1") (pinfunction "1_1") (pintype "input"))
      (node (ref "U2") (pin "3") (pinfunction "FB_3") (pintype "unspecified"))
    )
    (net (code "84") (name "Net-(U2-SW)") (class "Default")
      (node (ref "C3") (pin "2") (pinfunction "2_2") (pintype "input"))
      (node (ref "L2") (pin "2") (pinfunction "2_2") (pintype "unspecified"))
      (node (ref "U2") (pin "6") (pinfunction "SW_6") (pintype "unspecified"))
    )
    (net (code "85") (name "Net-(U6-A)") (class "Default")
      (node (ref "R44") (pin "1") (pinfunction "1_1") (pintype "input"))
      (node (ref "U6") (pin "2") (pinfunction "A_2") (pintype "unspecified"))
    )
    (net (code "86") (name "Net-(U9-FB)") (class "Default")
      (node (ref "R1") (pin "2") (pinfunction "2_2") (pintype "input"))
      (node (ref "R4") (pin "2") (pinfunction "2_2") (pintype "input"))
      (node (ref "U9") (pin "3") (pinfunction "FB_3") (pintype "unspecified"))
    )
    (net (code "87") (name "Net-(U12-K)") (class "Default")
      (node (ref "R66") (pin "2") (pinfunction "2_2") (pintype "input"))
      (node (ref "U12") (pin "1") (pinfunction "K_1") (pintype "unspecified"))
    )
    (net (code "88") (name "Net-(U13-K)") (class "Default")
      (node (ref "U13") (pin "1") (pinfunction "K_1") (pintype "unspecified"))
      (node (ref "U9") (pin "1") (pinfunction "VIN_1") (pintype "unspecified"))
    )
    (net (code "89") (name "Net-(U23-LEDA)") (class "Default")
      (node (ref "R81") (pin "2") (pinfunction "2_2") (pintype "input"))
      (node (ref "U23") (pin "12") (pinfunction "LEDA_12") (pintype "unspecified"))
    )
    (net (code "90") (name "Net-(U24-+IN2)") (class "Default")
      (node (ref "C71") (pin "2") (pinfunction "2_2") (pintype "input"))
      (node (ref "R2") (pin "2") (pinfunction "2_2") (pintype "input"))
      (node (ref "R3") (pin "1") (pinfunction "1_1") (pintype "input"))
      (node (ref "U24") (pin "5") (pinfunction "+IN2_5") (pintype "unspecified"))
    )
    (net (code "91") (name "Net-(U24--IN1)") (class "Default")
      (node (ref "R88") (pin "1") (pinfunction "1_1") (pintype "input"))
      (node (ref "U24") (pin "1") (pinfunction "OUTA_1") (pintype "unspecified"))
      (node (ref "U24") (pin "2") (pinfunction "-IN1_2") (pintype "unspecified"))
    )
    (net (code "92") (name "Net-(U24--IN2)") (class "Default")
      (node (ref "R6") (pin "1") (pinfunction "1_1") (pintype "input"))
      (node (ref "U24") (pin "6") (pinfunction "-IN2_6") (pintype "unspecified"))
      (node (ref "U24") (pin "7") (pinfunction "OUTB_7") (pintype "unspecified"))
    )
    (net (code "93") (name "Net-(U25-+IN1)") (class "Default")
      (node (ref "R25") (pin "1") (pinfunction "1_1") (pintype "input"))
      (node (ref "R54") (pin "2") (pinfunction "2_2") (pintype "unspecified"))
      (node (ref "U25") (pin "3") (pinfunction "+IN1_3") (pintype "unspecified"))
    )
    (net (code "94") (name "Net-(U25-+IN2)") (class "Default")
      (node (ref "R16") (pin "1") (pinfunction "1_1") (pintype "input"))
      (node (ref "R43") (pin "1") (pinfunction "1_1") (pintype "unspecified"))
      (node (ref "U25") (pin "5") (pinfunction "+IN2_5") (pintype "unspecified"))
    )
    (net (code "95") (name "Net-(U25--IN1)") (class "Default")
      (node (ref "R24") (pin "1") (pinfunction "1_1") (pintype "input"))
      (node (ref "R63") (pin "2") (pinfunction "2_2") (pintype "unspecified"))
      (node (ref "U25") (pin "2") (pinfunction "-IN1_2") (pintype "unspecified"))
    )
    (net (code "96") (name "Net-(U25--IN2)") (class "Default")
      (node (ref "R47") (pin "1") (pinfunction "1_1") (pintype "unspecified"))
      (node (ref "R8") (pin "2") (pinfunction "2_2") (pintype "input"))
      (node (ref "U25") (pin "6") (pinfunction "-IN2_6") (pintype "unspecified"))
    )
    (net (code "97") (name "Net-(U25-OUTA)") (class "Default")
      (node (ref "R24") (pin "2") (pinfunction "2_2") (pintype "input"))
      (node (ref "R57") (pin "1") (pinfunction "1_1") (pintype "input"))
      (node (ref "U25") (pin "1") (pinfunction "OUTA_1") (pintype "unspecified"))
    )
    (net (code "98") (name "Net-(U25-OUTB)") (class "Default")
      (node (ref "R65") (pin "1") (pinfunction "1_1") (pintype "input"))
      (node (ref "R8") (pin "1") (pinfunction "1_1") (pintype "input"))
      (node (ref "U25") (pin "7") (pinfunction "OUTB_7") (pintype "unspecified"))
    )
    (net (code "99") (name "PGND") (class "Default")
      (node (ref "CN1") (pin "2") (pinfunction "2_2") (pintype "unspecified"))
      (node (ref "Q6") (pin "1") (pinfunction "S_1") (pintype "unspecified"))
      (node (ref "Q6") (pin "2") (pinfunction "S_2") (pintype "unspecified"))
      (node (ref "Q6") (pin "3") (pinfunction "S_3") (pintype "unspecified"))
      (node (ref "Q8") (pin "1") (pinfunction "S_1") (pintype "unspecified"))
      (node (ref "Q8") (pin "2") (pinfunction "S_2") (pintype "unspecified"))
      (node (ref "Q8") (pin "3") (pinfunction "S_3") (pintype "unspecified"))
      (node (ref "R28") (pin "1") (pinfunction "1_1") (pintype "unspecified"))
      (node (ref "R29") (pin "1") (pinfunction "1_1") (pintype "unspecified"))
      (node (ref "R31") (pin "1") (pinfunction "1_1") (pintype "input"))
      (node (ref "R40") (pin "1") (pinfunction "1_1") (pintype "input"))
      (node (ref "R43") (pin "2") (pinfunction "2_2") (pintype "unspecified"))
      (node (ref "R54") (pin "1") (pinfunction "1_1") (pintype "unspecified"))
    )
    (net (code "100") (name "USB_5V") (class "Default")
      (node (ref "R35") (pin "2") (pinfunction "2_2") (pintype "input"))
      (node (ref "USB1") (pin "A4B9") (pinfunction "VBUS_A4B9") (pintype "unspecified"))
      (node (ref "USB1") (pin "B4A9") (pinfunction "VBUS_B4A9") (pintype "unspecified"))
    )
    (net (code "101") (name "VREF1.65") (class "Default")
      (node (ref "C76") (pin "2") (pinfunction "2_2") (pintype "input"))
      (node (ref "R16") (pin "2") (pinfunction "2_2") (pintype "input"))
      (node (ref "R25") (pin "2") (pinfunction "2_2") (pintype "input"))
      (node (ref "R6") (pin "2") (pinfunction "2_2") (pintype "input"))
    )
    (net (code "102") (name "unconnected-(R11-Pad4)") (class "Default")
      (node (ref "R11") (pin "4") (pinfunction "4_4") (pintype "unspecified+no_connect"))
    )
    (net (code "103") (name "unconnected-(R11-Pad5)") (class "Default")
      (node (ref "R11") (pin "5") (pinfunction "5_5") (pintype "unspecified+no_connect"))
    )
    (net (code "104") (name "unconnected-(SW1-Pad1)") (class "Default")
      (node (ref "SW1") (pin "1") (pinfunction "1_1") (pintype "unspecified+no_connect"))
    )
    (net (code "105") (name "unconnected-(SW1-Pad4)") (class "Default")
      (node (ref "SW1") (pin "4") (pinfunction "4_4") (pintype "unspecified+no_connect"))
    )
    (net (code "106") (name "unconnected-(SW2-Pad2)") (class "Default")
      (node (ref "SW2") (pin "2") (pinfunction "2_2") (pintype "unspecified+no_connect"))
    )
    (net (code "107") (name "unconnected-(SW2-Pad3)") (class "Default")
      (node (ref "SW2") (pin "3") (pinfunction "3_3") (pintype "unspecified+no_connect"))
    )
    (net (code "108") (name "unconnected-(SW3-Pad2)") (class "Default")
      (node (ref "SW3") (pin "2") (pinfunction "2_2") (pintype "unspecified+no_connect"))
    )
    (net (code "109") (name "unconnected-(SW3-Pad3)") (class "Default")
      (node (ref "SW3") (pin "3") (pinfunction "3_3") (pintype "unspecified+no_connect"))
    )
    (net (code "110") (name "unconnected-(U1-N{slash}C-Pad4)") (class "Default")
      (node (ref "U1") (pin "4") (pinfunction "N/C_4") (pintype "unspecified"))
    )
    (net (code "111") (name "unconnected-(U3-PA3-Pad17)") (class "Default")
      (node (ref "U3") (pin "17") (pinfunction "PA3_17") (pintype "unspecified+no_connect"))
    )
    (net (code "112") (name "unconnected-(U3-PA8-Pad42)") (class "Default")
      (node (ref "U3") (pin "42") (pinfunction "PA8_42") (pintype "unspecified+no_connect"))
    )
    (net (code "113") (name "unconnected-(U3-PA9-Pad43)") (class "Default")
      (node (ref "U3") (pin "43") (pinfunction "PA9_43") (pintype "unspecified+no_connect"))
    )
    (net (code "114") (name "unconnected-(U3-PA10-Pad44)") (class "Default")
      (node (ref "U3") (pin "44") (pinfunction "PA10_44") (pintype "unspecified+no_connect"))
    )
    (net (code "115") (name "unconnected-(U3-PA11-Pad45)") (class "Default")
      (node (ref "U3") (pin "45") (pinfunction "PA11_45") (pintype "unspecified+no_connect"))
    )
    (net (code "116") (name "unconnected-(U3-PA12-Pad46)") (class "Default")
      (node (ref "U3") (pin "46") (pinfunction "PA12_46") (pintype "unspecified+no_connect"))
    )
    (net (code "117") (name "unconnected-(U3-PB1-Pad25)") (class "Default")
      (node (ref "U3") (pin "25") (pinfunction "PB1_25") (pintype "unspecified+no_connect"))
    )
    (net (code "118") (name "unconnected-(U3-PB13-Pad35)") (class "Default")
      (node (ref "U3") (pin "35") (pinfunction "PB13_35") (pintype "unspecified+no_connect"))
    )
    (net (code "119") (name "unconnected-(U3-PB14-Pad36)") (class "Default")
      (node (ref "U3") (pin "36") (pinfunction "PB14_36") (pintype "unspecified+no_connect"))
    )
    (net (code "120") (name "unconnected-(U3-PC6-Pad38)") (class "Default")
      (node (ref "U3") (pin "38") (pinfunction "PC6_38") (pintype "unspecified+no_connect"))
    )
    (net (code "121") (name "unconnected-(U3-PC7-Pad39)") (class "Default")
      (node (ref "U3") (pin "39") (pinfunction "PC7_39") (pintype "unspecified+no_connect"))
    )
    (net (code "122") (name "unconnected-(U3-PC8-Pad40)") (class "Default")
      (node (ref "U3") (pin "40") (pinfunction "PC8_40") (pintype "unspecified+no_connect"))
    )
    (net (code "123") (name "unconnected-(U23-NC-Pad9)") (class "Default")
      (node (ref "U23") (pin "9") (pinfunction "NC_9") (pintype "unspecified+no_connect"))
    )
    (net (code "124") (name "unconnected-(U23-TP0-Pad1)") (class "Default")
      (node (ref "U23") (pin "1") (pinfunction "TP0_1") (pintype "unspecified+no_connect"))
    )
    (net (code "125") (name "unconnected-(U23-TP1-Pad2)") (class "Default")
      (node (ref "U23") (pin "2") (pinfunction "TP1_2") (pintype "unspecified+no_connect"))
    )
    (net (code "126") (name "unconnected-(U26-RTS#-Pad4)") (class "Default")
      (node (ref "U26") (pin "4") (pinfunction "RTS#_4") (pintype "unspecified+no_connect"))
    )
    (net (code "127") (name "unconnected-(USB1-CC1-PadA5)") (class "Default")
      (node (ref "USB1") (pin "A5") (pinfunction "CC1_A5") (pintype "unspecified+no_connect"))
    )
    (net (code "128") (name "unconnected-(USB1-CC2-PadB5)") (class "Default")
      (node (ref "USB1") (pin "B5") (pinfunction "CC2_B5") (pintype "unspecified+no_connect"))
    )
    (net (code "129") (name "unconnected-(USB1-SBU1-PadA8)") (class "Default")
      (node (ref "USB1") (pin "A8") (pinfunction "SBU1_A8") (pintype "unspecified+no_connect"))
    )
    (net (code "130") (name "unconnected-(USB1-SBU2-PadB8)") (class "Default")
      (node (ref "USB1") (pin "B8") (pinfunction "SBU2_B8") (pintype "unspecified+no_connect"))
    )
  )
)
